# LEDcontroller.net
KiCad netlist of a schematic drawn in Altium Designer
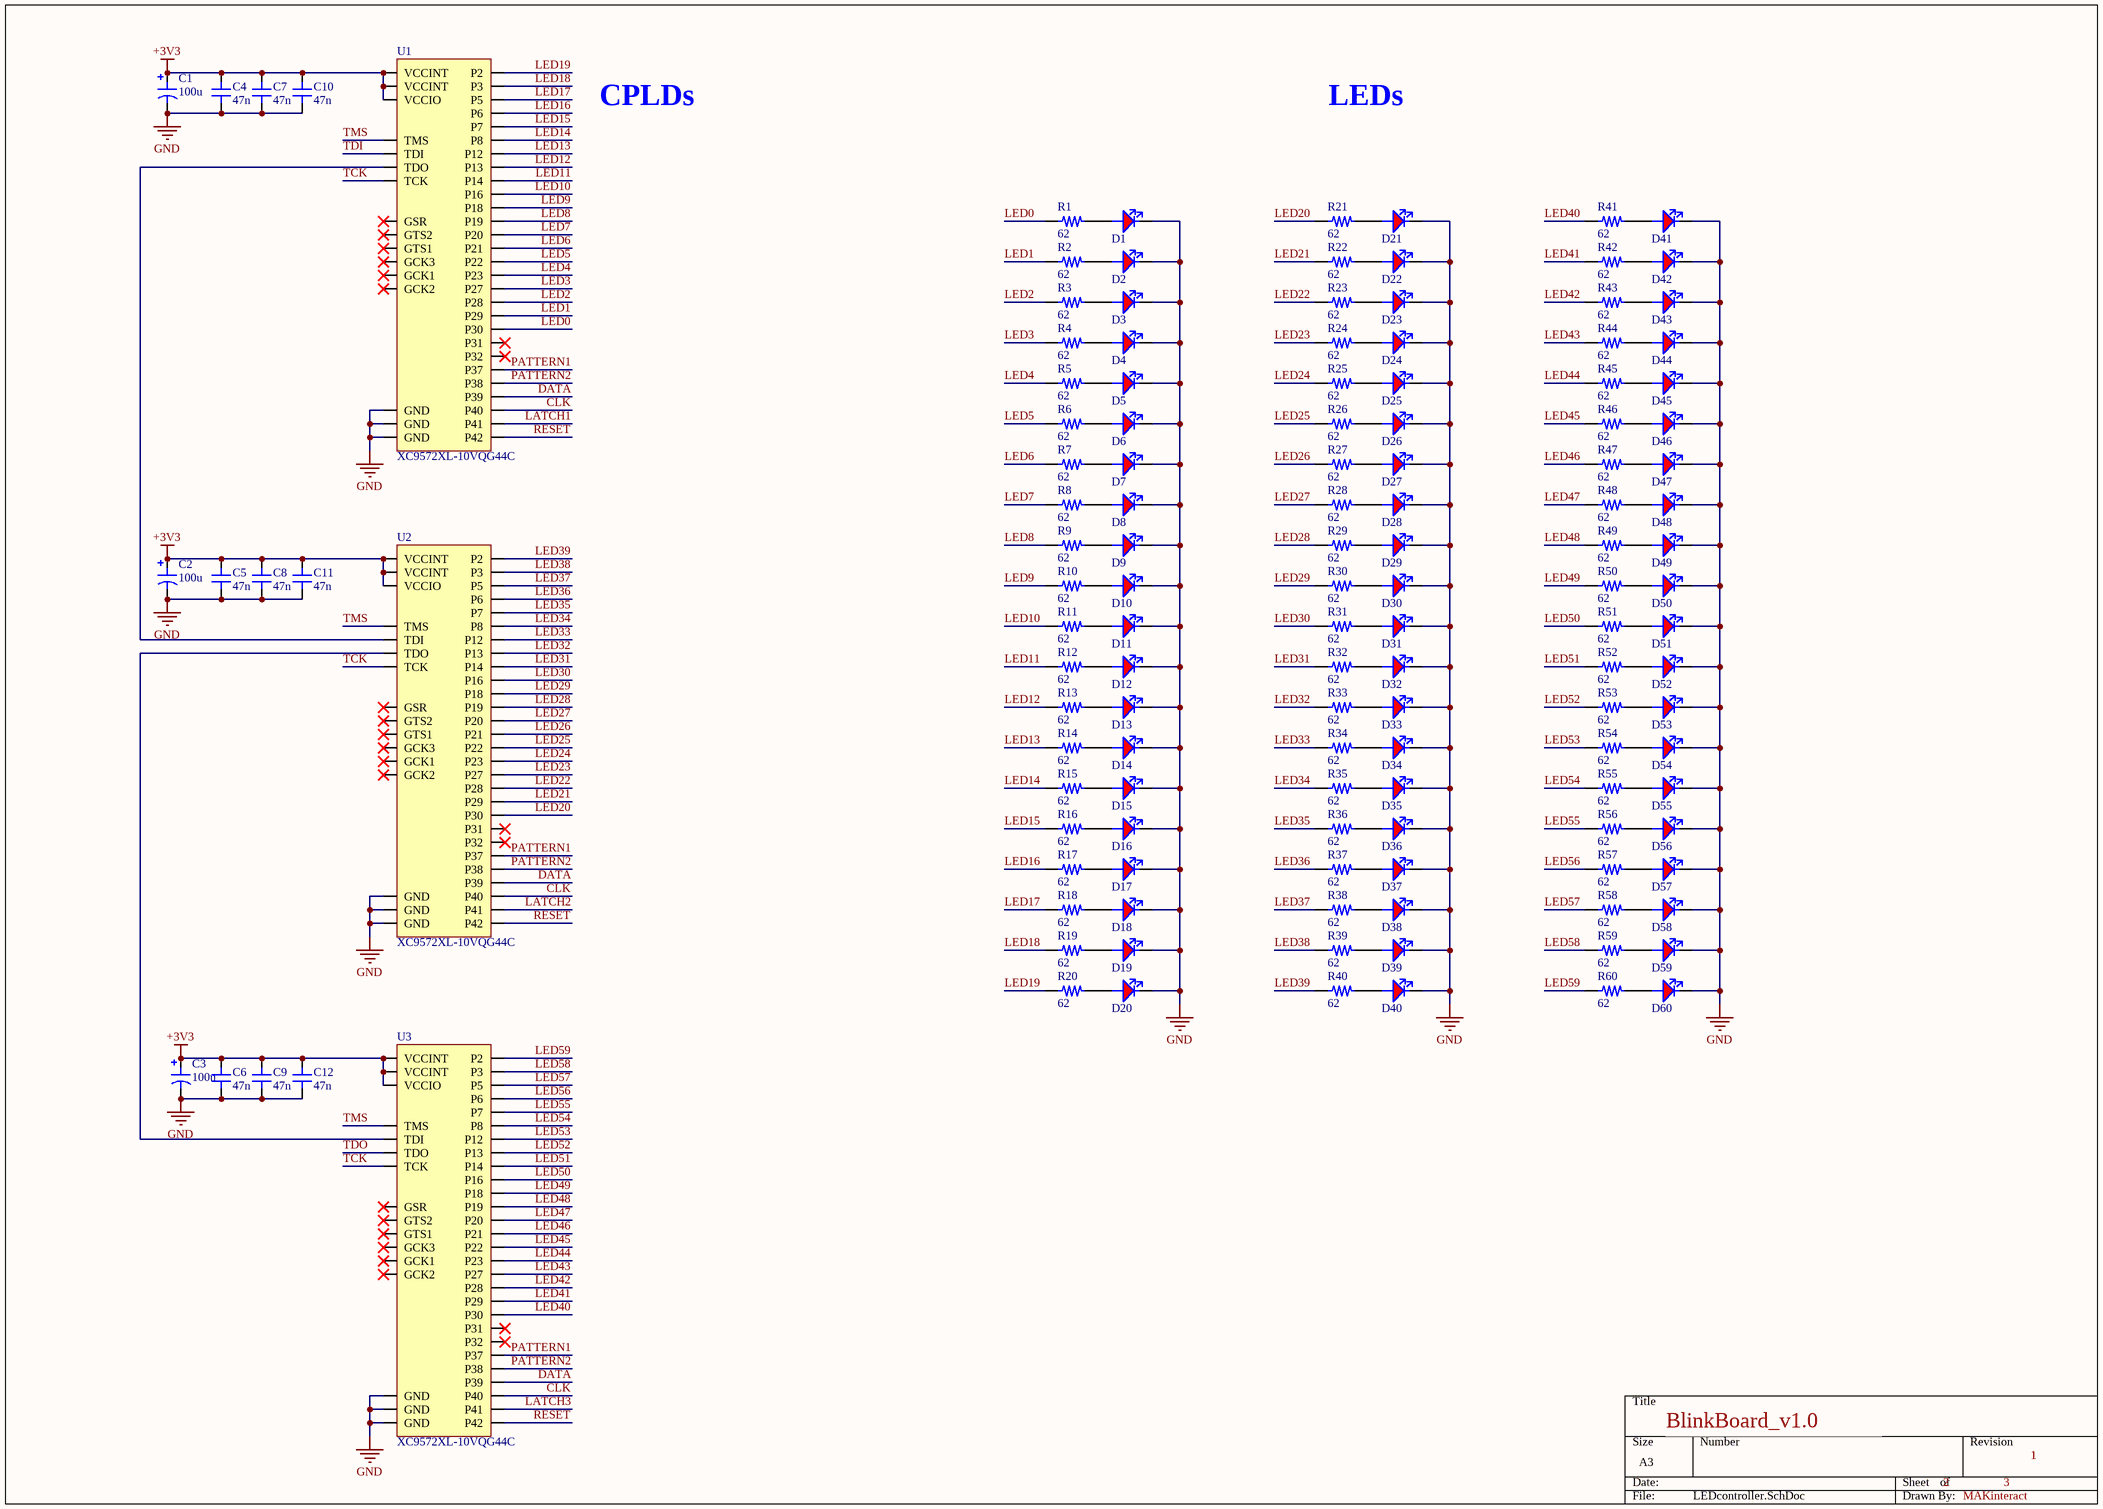
[diagram p0: LEDcontroller.SchDoc]

(export (version "E")
  (design (tool "Eeschema 10.0.6"))
  (components
    (comp (ref "C1")
      (value "100u")
      (footprint "C1206")
      (description "100uF Solid MnO2 Tantalum Capacitor,  4 V +/-20%,  T491 Series")
      (fields
        (field (name "MANUFACTURER") "KEMET")
        (field (name "MANUFACTURER PART NUMBER") "T491A107M004AT")
      )
      (libsource (lib "BlinkBoard") (part "C1206_100u"))
    )
    (comp (ref "C2")
      (value "100u")
      (footprint "C1206")
      (description "100uF Solid MnO2 Tantalum Capacitor,  4 V +/-20%,  T491 Series")
      (fields
        (field (name "MANUFACTURER") "KEMET")
        (field (name "MANUFACTURER PART NUMBER") "T491A107M004AT")
      )
      (libsource (lib "BlinkBoard") (part "C1206_100u"))
    )
    (comp (ref "C3")
      (value "100u")
      (footprint "C1206")
      (description "100uF Solid MnO2 Tantalum Capacitor,  4 V +/-20%,  T491 Series")
      (fields
        (field (name "MANUFACTURER") "KEMET")
        (field (name "MANUFACTURER PART NUMBER") "T491A107M004AT")
      )
      (libsource (lib "BlinkBoard") (part "C1206_100u"))
    )
    (comp (ref "C4")
      (value "47n")
      (footprint "C0805")
      (description "Cap Ceramic 0.047uF 50V X7R 5% SMD 0805 125C Paper T/R")
      (fields
        (field (name "MANUFACTURER") "Yageo")
        (field (name "MANUFACTURER PART NUMBER") "CC0805JRX7R9BB473")
      )
      (libsource (lib "LightBoard_v1.0") (part "C0805_47n"))
    )
    (comp (ref "C5")
      (value "47n")
      (footprint "C0805")
      (description "Cap Ceramic 0.047uF 50V X7R 5% SMD 0805 125C Paper T/R")
      (fields
        (field (name "MANUFACTURER") "Yageo")
        (field (name "MANUFACTURER PART NUMBER") "CC0805JRX7R9BB473")
      )
      (libsource (lib "LightBoard_v1.0") (part "C0805_47n"))
    )
    (comp (ref "C6")
      (value "47n")
      (footprint "C0805")
      (description "Cap Ceramic 0.047uF 50V X7R 5% SMD 0805 125C Paper T/R")
      (fields
        (field (name "MANUFACTURER") "Yageo")
        (field (name "MANUFACTURER PART NUMBER") "CC0805JRX7R9BB473")
      )
      (libsource (lib "LightBoard_v1.0") (part "C0805_47n"))
    )
    (comp (ref "C7")
      (value "47n")
      (footprint "C0805")
      (description "Cap Ceramic 0.047uF 50V X7R 5% SMD 0805 125C Paper T/R")
      (fields
        (field (name "MANUFACTURER") "Yageo")
        (field (name "MANUFACTURER PART NUMBER") "CC0805JRX7R9BB473")
      )
      (libsource (lib "LightBoard_v1.0") (part "C0805_47n"))
    )
    (comp (ref "C8")
      (value "47n")
      (footprint "C0805")
      (description "Cap Ceramic 0.047uF 50V X7R 5% SMD 0805 125C Paper T/R")
      (fields
        (field (name "MANUFACTURER") "Yageo")
        (field (name "MANUFACTURER PART NUMBER") "CC0805JRX7R9BB473")
      )
      (libsource (lib "LightBoard_v1.0") (part "C0805_47n"))
    )
    (comp (ref "C9")
      (value "47n")
      (footprint "C0805")
      (description "Cap Ceramic 0.047uF 50V X7R 5% SMD 0805 125C Paper T/R")
      (fields
        (field (name "MANUFACTURER") "Yageo")
        (field (name "MANUFACTURER PART NUMBER") "CC0805JRX7R9BB473")
      )
      (libsource (lib "LightBoard_v1.0") (part "C0805_47n"))
    )
    (comp (ref "C10")
      (value "47n")
      (footprint "C0805")
      (description "Cap Ceramic 0.047uF 50V X7R 5% SMD 0805 125C Paper T/R")
      (fields
        (field (name "MANUFACTURER") "Yageo")
        (field (name "MANUFACTURER PART NUMBER") "CC0805JRX7R9BB473")
      )
      (libsource (lib "LightBoard_v1.0") (part "C0805_47n"))
    )
    (comp (ref "C11")
      (value "47n")
      (footprint "C0805")
      (description "Cap Ceramic 0.047uF 50V X7R 5% SMD 0805 125C Paper T/R")
      (fields
        (field (name "MANUFACTURER") "Yageo")
        (field (name "MANUFACTURER PART NUMBER") "CC0805JRX7R9BB473")
      )
      (libsource (lib "LightBoard_v1.0") (part "C0805_47n"))
    )
    (comp (ref "C12")
      (value "47n")
      (footprint "C0805")
      (description "Cap Ceramic 0.047uF 50V X7R 5% SMD 0805 125C Paper T/R")
      (fields
        (field (name "MANUFACTURER") "Yageo")
        (field (name "MANUFACTURER PART NUMBER") "CC0805JRX7R9BB473")
      )
      (libsource (lib "LightBoard_v1.0") (part "C0805_47n"))
    )
    (comp (ref "D1")
      (value "LED0402_RED")
      (footprint "LED0402")
      (description "Led red")
      (fields
        (field (name "MANUFACTURER") "Everlight")
        (field (name "MANUFACTURER PART NUMBER") "EAST1005BA0")
      )
      (libsource (lib "LightBoard_v1.0") (part "LED0402_RED"))
    )
    (comp (ref "D2")
      (value "LED0402_RED")
      (footprint "LED0402")
      (description "Led red")
      (fields
        (field (name "MANUFACTURER") "Everlight")
        (field (name "MANUFACTURER PART NUMBER") "EAST1005BA0")
      )
      (libsource (lib "LightBoard_v1.0") (part "LED0402_RED"))
    )
    (comp (ref "D3")
      (value "LED0402_RED")
      (footprint "LED0402")
      (description "Led red")
      (fields
        (field (name "MANUFACTURER") "Everlight")
        (field (name "MANUFACTURER PART NUMBER") "EAST1005BA0")
      )
      (libsource (lib "LightBoard_v1.0") (part "LED0402_RED"))
    )
    (comp (ref "D4")
      (value "LED0402_RED")
      (footprint "LED0402")
      (description "Led red")
      (fields
        (field (name "MANUFACTURER") "Everlight")
        (field (name "MANUFACTURER PART NUMBER") "EAST1005BA0")
      )
      (libsource (lib "LightBoard_v1.0") (part "LED0402_RED"))
    )
    (comp (ref "D5")
      (value "LED0402_RED")
      (footprint "LED0402")
      (description "Led red")
      (fields
        (field (name "MANUFACTURER") "Everlight")
        (field (name "MANUFACTURER PART NUMBER") "EAST1005BA0")
      )
      (libsource (lib "LightBoard_v1.0") (part "LED0402_RED"))
    )
    (comp (ref "D6")
      (value "LED0402_RED")
      (footprint "LED0402")
      (description "Led red")
      (fields
        (field (name "MANUFACTURER") "Everlight")
        (field (name "MANUFACTURER PART NUMBER") "EAST1005BA0")
      )
      (libsource (lib "LightBoard_v1.0") (part "LED0402_RED"))
    )
    (comp (ref "D7")
      (value "LED0402_RED")
      (footprint "LED0402")
      (description "Led red")
      (fields
        (field (name "MANUFACTURER") "Everlight")
        (field (name "MANUFACTURER PART NUMBER") "EAST1005BA0")
      )
      (libsource (lib "LightBoard_v1.0") (part "LED0402_RED"))
    )
    (comp (ref "D8")
      (value "LED0402_RED")
      (footprint "LED0402")
      (description "Led red")
      (fields
        (field (name "MANUFACTURER") "Everlight")
        (field (name "MANUFACTURER PART NUMBER") "EAST1005BA0")
      )
      (libsource (lib "LightBoard_v1.0") (part "LED0402_RED"))
    )
    (comp (ref "D9")
      (value "LED0402_RED")
      (footprint "LED0402")
      (description "Led red")
      (fields
        (field (name "MANUFACTURER") "Everlight")
        (field (name "MANUFACTURER PART NUMBER") "EAST1005BA0")
      )
      (libsource (lib "LightBoard_v1.0") (part "LED0402_RED"))
    )
    (comp (ref "D10")
      (value "LED0402_RED")
      (footprint "LED0402")
      (description "Led red")
      (fields
        (field (name "MANUFACTURER") "Everlight")
        (field (name "MANUFACTURER PART NUMBER") "EAST1005BA0")
      )
      (libsource (lib "LightBoard_v1.0") (part "LED0402_RED"))
    )
    (comp (ref "D11")
      (value "LED0402_RED")
      (footprint "LED0402")
      (description "Led red")
      (fields
        (field (name "MANUFACTURER") "Everlight")
        (field (name "MANUFACTURER PART NUMBER") "EAST1005BA0")
      )
      (libsource (lib "LightBoard_v1.0") (part "LED0402_RED"))
    )
    (comp (ref "D12")
      (value "LED0402_RED")
      (footprint "LED0402")
      (description "Led red")
      (fields
        (field (name "MANUFACTURER") "Everlight")
        (field (name "MANUFACTURER PART NUMBER") "EAST1005BA0")
      )
      (libsource (lib "LightBoard_v1.0") (part "LED0402_RED"))
    )
    (comp (ref "D13")
      (value "LED0402_RED")
      (footprint "LED0402")
      (description "Led red")
      (fields
        (field (name "MANUFACTURER") "Everlight")
        (field (name "MANUFACTURER PART NUMBER") "EAST1005BA0")
      )
      (libsource (lib "LightBoard_v1.0") (part "LED0402_RED"))
    )
    (comp (ref "D14")
      (value "LED0402_RED")
      (footprint "LED0402")
      (description "Led red")
      (fields
        (field (name "MANUFACTURER") "Everlight")
        (field (name "MANUFACTURER PART NUMBER") "EAST1005BA0")
      )
      (libsource (lib "LightBoard_v1.0") (part "LED0402_RED"))
    )
    (comp (ref "D15")
      (value "LED0402_RED")
      (footprint "LED0402")
      (description "Led red")
      (fields
        (field (name "MANUFACTURER") "Everlight")
        (field (name "MANUFACTURER PART NUMBER") "EAST1005BA0")
      )
      (libsource (lib "LightBoard_v1.0") (part "LED0402_RED"))
    )
    (comp (ref "D16")
      (value "LED0402_RED")
      (footprint "LED0402")
      (description "Led red")
      (fields
        (field (name "MANUFACTURER") "Everlight")
        (field (name "MANUFACTURER PART NUMBER") "EAST1005BA0")
      )
      (libsource (lib "LightBoard_v1.0") (part "LED0402_RED"))
    )
    (comp (ref "D17")
      (value "LED0402_RED")
      (footprint "LED0402")
      (description "Led red")
      (fields
        (field (name "MANUFACTURER") "Everlight")
        (field (name "MANUFACTURER PART NUMBER") "EAST1005BA0")
      )
      (libsource (lib "LightBoard_v1.0") (part "LED0402_RED"))
    )
    (comp (ref "D18")
      (value "LED0402_RED")
      (footprint "LED0402")
      (description "Led red")
      (fields
        (field (name "MANUFACTURER") "Everlight")
        (field (name "MANUFACTURER PART NUMBER") "EAST1005BA0")
      )
      (libsource (lib "LightBoard_v1.0") (part "LED0402_RED"))
    )
    (comp (ref "D19")
      (value "LED0402_RED")
      (footprint "LED0402")
      (description "Led red")
      (fields
        (field (name "MANUFACTURER") "Everlight")
        (field (name "MANUFACTURER PART NUMBER") "EAST1005BA0")
      )
      (libsource (lib "LightBoard_v1.0") (part "LED0402_RED"))
    )
    (comp (ref "D20")
      (value "LED0402_RED")
      (footprint "LED0402")
      (description "Led red")
      (fields
        (field (name "MANUFACTURER") "Everlight")
        (field (name "MANUFACTURER PART NUMBER") "EAST1005BA0")
      )
      (libsource (lib "LightBoard_v1.0") (part "LED0402_RED"))
    )
    (comp (ref "D21")
      (value "LED0402_RED")
      (footprint "LED0402")
      (description "Led red")
      (fields
        (field (name "MANUFACTURER") "Everlight")
        (field (name "MANUFACTURER PART NUMBER") "EAST1005BA0")
      )
      (libsource (lib "LightBoard_v1.0") (part "LED0402_RED"))
    )
    (comp (ref "D22")
      (value "LED0402_RED")
      (footprint "LED0402")
      (description "Led red")
      (fields
        (field (name "MANUFACTURER") "Everlight")
        (field (name "MANUFACTURER PART NUMBER") "EAST1005BA0")
      )
      (libsource (lib "LightBoard_v1.0") (part "LED0402_RED"))
    )
    (comp (ref "D23")
      (value "LED0402_RED")
      (footprint "LED0402")
      (description "Led red")
      (fields
        (field (name "MANUFACTURER") "Everlight")
        (field (name "MANUFACTURER PART NUMBER") "EAST1005BA0")
      )
      (libsource (lib "LightBoard_v1.0") (part "LED0402_RED"))
    )
    (comp (ref "D24")
      (value "LED0402_RED")
      (footprint "LED0402")
      (description "Led red")
      (fields
        (field (name "MANUFACTURER") "Everlight")
        (field (name "MANUFACTURER PART NUMBER") "EAST1005BA0")
      )
      (libsource (lib "LightBoard_v1.0") (part "LED0402_RED"))
    )
    (comp (ref "D25")
      (value "LED0402_RED")
      (footprint "LED0402")
      (description "Led red")
      (fields
        (field (name "MANUFACTURER") "Everlight")
        (field (name "MANUFACTURER PART NUMBER") "EAST1005BA0")
      )
      (libsource (lib "LightBoard_v1.0") (part "LED0402_RED"))
    )
    (comp (ref "D26")
      (value "LED0402_RED")
      (footprint "LED0402")
      (description "Led red")
      (fields
        (field (name "MANUFACTURER") "Everlight")
        (field (name "MANUFACTURER PART NUMBER") "EAST1005BA0")
      )
      (libsource (lib "LightBoard_v1.0") (part "LED0402_RED"))
    )
    (comp (ref "D27")
      (value "LED0402_RED")
      (footprint "LED0402")
      (description "Led red")
      (fields
        (field (name "MANUFACTURER") "Everlight")
        (field (name "MANUFACTURER PART NUMBER") "EAST1005BA0")
      )
      (libsource (lib "LightBoard_v1.0") (part "LED0402_RED"))
    )
    (comp (ref "D28")
      (value "LED0402_RED")
      (footprint "LED0402")
      (description "Led red")
      (fields
        (field (name "MANUFACTURER") "Everlight")
        (field (name "MANUFACTURER PART NUMBER") "EAST1005BA0")
      )
      (libsource (lib "LightBoard_v1.0") (part "LED0402_RED"))
    )
    (comp (ref "D29")
      (value "LED0402_RED")
      (footprint "LED0402")
      (description "Led red")
      (fields
        (field (name "MANUFACTURER") "Everlight")
        (field (name "MANUFACTURER PART NUMBER") "EAST1005BA0")
      )
      (libsource (lib "LightBoard_v1.0") (part "LED0402_RED"))
    )
    (comp (ref "D30")
      (value "LED0402_RED")
      (footprint "LED0402")
      (description "Led red")
      (fields
        (field (name "MANUFACTURER") "Everlight")
        (field (name "MANUFACTURER PART NUMBER") "EAST1005BA0")
      )
      (libsource (lib "LightBoard_v1.0") (part "LED0402_RED"))
    )
    (comp (ref "D31")
      (value "LED0402_RED")
      (footprint "LED0402")
      (description "Led red")
      (fields
        (field (name "MANUFACTURER") "Everlight")
        (field (name "MANUFACTURER PART NUMBER") "EAST1005BA0")
      )
      (libsource (lib "LightBoard_v1.0") (part "LED0402_RED"))
    )
    (comp (ref "D32")
      (value "LED0402_RED")
      (footprint "LED0402")
      (description "Led red")
      (fields
        (field (name "MANUFACTURER") "Everlight")
        (field (name "MANUFACTURER PART NUMBER") "EAST1005BA0")
      )
      (libsource (lib "LightBoard_v1.0") (part "LED0402_RED"))
    )
    (comp (ref "D33")
      (value "LED0402_RED")
      (footprint "LED0402")
      (description "Led red")
      (fields
        (field (name "MANUFACTURER") "Everlight")
        (field (name "MANUFACTURER PART NUMBER") "EAST1005BA0")
      )
      (libsource (lib "LightBoard_v1.0") (part "LED0402_RED"))
    )
    (comp (ref "D34")
      (value "LED0402_RED")
      (footprint "LED0402")
      (description "Led red")
      (fields
        (field (name "MANUFACTURER") "Everlight")
        (field (name "MANUFACTURER PART NUMBER") "EAST1005BA0")
      )
      (libsource (lib "LightBoard_v1.0") (part "LED0402_RED"))
    )
    (comp (ref "D35")
      (value "LED0402_RED")
      (footprint "LED0402")
      (description "Led red")
      (fields
        (field (name "MANUFACTURER") "Everlight")
        (field (name "MANUFACTURER PART NUMBER") "EAST1005BA0")
      )
      (libsource (lib "LightBoard_v1.0") (part "LED0402_RED"))
    )
    (comp (ref "D36")
      (value "LED0402_RED")
      (footprint "LED0402")
      (description "Led red")
      (fields
        (field (name "MANUFACTURER") "Everlight")
        (field (name "MANUFACTURER PART NUMBER") "EAST1005BA0")
      )
      (libsource (lib "LightBoard_v1.0") (part "LED0402_RED"))
    )
    (comp (ref "D37")
      (value "LED0402_RED")
      (footprint "LED0402")
      (description "Led red")
      (fields
        (field (name "MANUFACTURER") "Everlight")
        (field (name "MANUFACTURER PART NUMBER") "EAST1005BA0")
      )
      (libsource (lib "LightBoard_v1.0") (part "LED0402_RED"))
    )
    (comp (ref "D38")
      (value "LED0402_RED")
      (footprint "LED0402")
      (description "Led red")
      (fields
        (field (name "MANUFACTURER") "Everlight")
        (field (name "MANUFACTURER PART NUMBER") "EAST1005BA0")
      )
      (libsource (lib "LightBoard_v1.0") (part "LED0402_RED"))
    )
    (comp (ref "D39")
      (value "LED0402_RED")
      (footprint "LED0402")
      (description "Led red")
      (fields
        (field (name "MANUFACTURER") "Everlight")
        (field (name "MANUFACTURER PART NUMBER") "EAST1005BA0")
      )
      (libsource (lib "LightBoard_v1.0") (part "LED0402_RED"))
    )
    (comp (ref "D40")
      (value "LED0402_RED")
      (footprint "LED0402")
      (description "Led red")
      (fields
        (field (name "MANUFACTURER") "Everlight")
        (field (name "MANUFACTURER PART NUMBER") "EAST1005BA0")
      )
      (libsource (lib "LightBoard_v1.0") (part "LED0402_RED"))
    )
    (comp (ref "D41")
      (value "LED0402_RED")
      (footprint "LED0402")
      (description "Led red")
      (fields
        (field (name "MANUFACTURER") "Everlight")
        (field (name "MANUFACTURER PART NUMBER") "EAST1005BA0")
      )
      (libsource (lib "LightBoard_v1.0") (part "LED0402_RED"))
    )
    (comp (ref "D42")
      (value "LED0402_RED")
      (footprint "LED0402")
      (description "Led red")
      (fields
        (field (name "MANUFACTURER") "Everlight")
        (field (name "MANUFACTURER PART NUMBER") "EAST1005BA0")
      )
      (libsource (lib "LightBoard_v1.0") (part "LED0402_RED"))
    )
    (comp (ref "D43")
      (value "LED0402_RED")
      (footprint "LED0402")
      (description "Led red")
      (fields
        (field (name "MANUFACTURER") "Everlight")
        (field (name "MANUFACTURER PART NUMBER") "EAST1005BA0")
      )
      (libsource (lib "LightBoard_v1.0") (part "LED0402_RED"))
    )
    (comp (ref "D44")
      (value "LED0402_RED")
      (footprint "LED0402")
      (description "Led red")
      (fields
        (field (name "MANUFACTURER") "Everlight")
        (field (name "MANUFACTURER PART NUMBER") "EAST1005BA0")
      )
      (libsource (lib "LightBoard_v1.0") (part "LED0402_RED"))
    )
    (comp (ref "D45")
      (value "LED0402_RED")
      (footprint "LED0402")
      (description "Led red")
      (fields
        (field (name "MANUFACTURER") "Everlight")
        (field (name "MANUFACTURER PART NUMBER") "EAST1005BA0")
      )
      (libsource (lib "LightBoard_v1.0") (part "LED0402_RED"))
    )
    (comp (ref "D46")
      (value "LED0402_RED")
      (footprint "LED0402")
      (description "Led red")
      (fields
        (field (name "MANUFACTURER") "Everlight")
        (field (name "MANUFACTURER PART NUMBER") "EAST1005BA0")
      )
      (libsource (lib "LightBoard_v1.0") (part "LED0402_RED"))
    )
    (comp (ref "D47")
      (value "LED0402_RED")
      (footprint "LED0402")
      (description "Led red")
      (fields
        (field (name "MANUFACTURER") "Everlight")
        (field (name "MANUFACTURER PART NUMBER") "EAST1005BA0")
      )
      (libsource (lib "LightBoard_v1.0") (part "LED0402_RED"))
    )
    (comp (ref "D48")
      (value "LED0402_RED")
      (footprint "LED0402")
      (description "Led red")
      (fields
        (field (name "MANUFACTURER") "Everlight")
        (field (name "MANUFACTURER PART NUMBER") "EAST1005BA0")
      )
      (libsource (lib "LightBoard_v1.0") (part "LED0402_RED"))
    )
    (comp (ref "D49")
      (value "LED0402_RED")
      (footprint "LED0402")
      (description "Led red")
      (fields
        (field (name "MANUFACTURER") "Everlight")
        (field (name "MANUFACTURER PART NUMBER") "EAST1005BA0")
      )
      (libsource (lib "LightBoard_v1.0") (part "LED0402_RED"))
    )
    (comp (ref "D50")
      (value "LED0402_RED")
      (footprint "LED0402")
      (description "Led red")
      (fields
        (field (name "MANUFACTURER") "Everlight")
        (field (name "MANUFACTURER PART NUMBER") "EAST1005BA0")
      )
      (libsource (lib "LightBoard_v1.0") (part "LED0402_RED"))
    )
    (comp (ref "D51")
      (value "LED0402_RED")
      (footprint "LED0402")
      (description "Led red")
      (fields
        (field (name "MANUFACTURER") "Everlight")
        (field (name "MANUFACTURER PART NUMBER") "EAST1005BA0")
      )
      (libsource (lib "LightBoard_v1.0") (part "LED0402_RED"))
    )
    (comp (ref "D52")
      (value "LED0402_RED")
      (footprint "LED0402")
      (description "Led red")
      (fields
        (field (name "MANUFACTURER") "Everlight")
        (field (name "MANUFACTURER PART NUMBER") "EAST1005BA0")
      )
      (libsource (lib "LightBoard_v1.0") (part "LED0402_RED"))
    )
    (comp (ref "D53")
      (value "LED0402_RED")
      (footprint "LED0402")
      (description "Led red")
      (fields
        (field (name "MANUFACTURER") "Everlight")
        (field (name "MANUFACTURER PART NUMBER") "EAST1005BA0")
      )
      (libsource (lib "LightBoard_v1.0") (part "LED0402_RED"))
    )
    (comp (ref "D54")
      (value "LED0402_RED")
      (footprint "LED0402")
      (description "Led red")
      (fields
        (field (name "MANUFACTURER") "Everlight")
        (field (name "MANUFACTURER PART NUMBER") "EAST1005BA0")
      )
      (libsource (lib "LightBoard_v1.0") (part "LED0402_RED"))
    )
    (comp (ref "D55")
      (value "LED0402_RED")
      (footprint "LED0402")
      (description "Led red")
      (fields
        (field (name "MANUFACTURER") "Everlight")
        (field (name "MANUFACTURER PART NUMBER") "EAST1005BA0")
      )
      (libsource (lib "LightBoard_v1.0") (part "LED0402_RED"))
    )
    (comp (ref "D56")
      (value "LED0402_RED")
      (footprint "LED0402")
      (description "Led red")
      (fields
        (field (name "MANUFACTURER") "Everlight")
        (field (name "MANUFACTURER PART NUMBER") "EAST1005BA0")
      )
      (libsource (lib "LightBoard_v1.0") (part "LED0402_RED"))
    )
    (comp (ref "D57")
      (value "LED0402_RED")
      (footprint "LED0402")
      (description "Led red")
      (fields
        (field (name "MANUFACTURER") "Everlight")
        (field (name "MANUFACTURER PART NUMBER") "EAST1005BA0")
      )
      (libsource (lib "LightBoard_v1.0") (part "LED0402_RED"))
    )
    (comp (ref "D58")
      (value "LED0402_RED")
      (footprint "LED0402")
      (description "Led red")
      (fields
        (field (name "MANUFACTURER") "Everlight")
        (field (name "MANUFACTURER PART NUMBER") "EAST1005BA0")
      )
      (libsource (lib "LightBoard_v1.0") (part "LED0402_RED"))
    )
    (comp (ref "D59")
      (value "LED0402_RED")
      (footprint "LED0402")
      (description "Led red")
      (fields
        (field (name "MANUFACTURER") "Everlight")
        (field (name "MANUFACTURER PART NUMBER") "EAST1005BA0")
      )
      (libsource (lib "LightBoard_v1.0") (part "LED0402_RED"))
    )
    (comp (ref "D60")
      (value "LED0402_RED")
      (footprint "LED0402")
      (description "Led red")
      (fields
        (field (name "MANUFACTURER") "Everlight")
        (field (name "MANUFACTURER PART NUMBER") "EAST1005BA0")
      )
      (libsource (lib "LightBoard_v1.0") (part "LED0402_RED"))
    )
    (comp (ref "R1")
      (value "62")
      (footprint "RES0402")
      (description "RES SMD 62 OHM 1% 1/16W 0402")
      (fields
        (field (name "MANUFACTURER") "Yageo")
        (field (name "MANUFACTURER PART NUMBER") "RC0402FR-0762RL")
      )
      (libsource (lib "LightBoard_v1.0") (part "R0402_62"))
    )
    (comp (ref "R2")
      (value "62")
      (footprint "RES0402")
      (description "RES SMD 62 OHM 1% 1/16W 0402")
      (fields
        (field (name "MANUFACTURER") "Yageo")
        (field (name "MANUFACTURER PART NUMBER") "RC0402FR-0762RL")
      )
      (libsource (lib "LightBoard_v1.0") (part "R0402_62"))
    )
    (comp (ref "R3")
      (value "62")
      (footprint "RES0402")
      (description "RES SMD 62 OHM 1% 1/16W 0402")
      (fields
        (field (name "MANUFACTURER") "Yageo")
        (field (name "MANUFACTURER PART NUMBER") "RC0402FR-0762RL")
      )
      (libsource (lib "LightBoard_v1.0") (part "R0402_62"))
    )
    (comp (ref "R4")
      (value "62")
      (footprint "RES0402")
      (description "RES SMD 62 OHM 1% 1/16W 0402")
      (fields
        (field (name "MANUFACTURER") "Yageo")
        (field (name "MANUFACTURER PART NUMBER") "RC0402FR-0762RL")
      )
      (libsource (lib "LightBoard_v1.0") (part "R0402_62"))
    )
    (comp (ref "R5")
      (value "62")
      (footprint "RES0402")
      (description "RES SMD 62 OHM 1% 1/16W 0402")
      (fields
        (field (name "MANUFACTURER") "Yageo")
        (field (name "MANUFACTURER PART NUMBER") "RC0402FR-0762RL")
      )
      (libsource (lib "LightBoard_v1.0") (part "R0402_62"))
    )
    (comp (ref "R6")
      (value "62")
      (footprint "RES0402")
      (description "RES SMD 62 OHM 1% 1/16W 0402")
      (fields
        (field (name "MANUFACTURER") "Yageo")
        (field (name "MANUFACTURER PART NUMBER") "RC0402FR-0762RL")
      )
      (libsource (lib "LightBoard_v1.0") (part "R0402_62"))
    )
    (comp (ref "R7")
      (value "62")
      (footprint "RES0402")
      (description "RES SMD 62 OHM 1% 1/16W 0402")
      (fields
        (field (name "MANUFACTURER") "Yageo")
        (field (name "MANUFACTURER PART NUMBER") "RC0402FR-0762RL")
      )
      (libsource (lib "LightBoard_v1.0") (part "R0402_62"))
    )
    (comp (ref "R8")
      (value "62")
      (footprint "RES0402")
      (description "RES SMD 62 OHM 1% 1/16W 0402")
      (fields
        (field (name "MANUFACTURER") "Yageo")
        (field (name "MANUFACTURER PART NUMBER") "RC0402FR-0762RL")
      )
      (libsource (lib "LightBoard_v1.0") (part "R0402_62"))
    )
    (comp (ref "R9")
      (value "62")
      (footprint "RES0402")
      (description "RES SMD 62 OHM 1% 1/16W 0402")
      (fields
        (field (name "MANUFACTURER") "Yageo")
        (field (name "MANUFACTURER PART NUMBER") "RC0402FR-0762RL")
      )
      (libsource (lib "LightBoard_v1.0") (part "R0402_62"))
    )
    (comp (ref "R10")
      (value "62")
      (footprint "RES0402")
      (description "RES SMD 62 OHM 1% 1/16W 0402")
      (fields
        (field (name "MANUFACTURER") "Yageo")
        (field (name "MANUFACTURER PART NUMBER") "RC0402FR-0762RL")
      )
      (libsource (lib "LightBoard_v1.0") (part "R0402_62"))
    )
    (comp (ref "R11")
      (value "62")
      (footprint "RES0402")
      (description "RES SMD 62 OHM 1% 1/16W 0402")
      (fields
        (field (name "MANUFACTURER") "Yageo")
        (field (name "MANUFACTURER PART NUMBER") "RC0402FR-0762RL")
      )
      (libsource (lib "LightBoard_v1.0") (part "R0402_62"))
    )
    (comp (ref "R12")
      (value "62")
      (footprint "RES0402")
      (description "RES SMD 62 OHM 1% 1/16W 0402")
      (fields
        (field (name "MANUFACTURER") "Yageo")
        (field (name "MANUFACTURER PART NUMBER") "RC0402FR-0762RL")
      )
      (libsource (lib "LightBoard_v1.0") (part "R0402_62"))
    )
    (comp (ref "R13")
      (value "62")
      (footprint "RES0402")
      (description "RES SMD 62 OHM 1% 1/16W 0402")
      (fields
        (field (name "MANUFACTURER") "Yageo")
        (field (name "MANUFACTURER PART NUMBER") "RC0402FR-0762RL")
      )
      (libsource (lib "LightBoard_v1.0") (part "R0402_62"))
    )
    (comp (ref "R14")
      (value "62")
      (footprint "RES0402")
      (description "RES SMD 62 OHM 1% 1/16W 0402")
      (fields
        (field (name "MANUFACTURER") "Yageo")
        (field (name "MANUFACTURER PART NUMBER") "RC0402FR-0762RL")
      )
      (libsource (lib "LightBoard_v1.0") (part "R0402_62"))
    )
    (comp (ref "R15")
      (value "62")
      (footprint "RES0402")
      (description "RES SMD 62 OHM 1% 1/16W 0402")
      (fields
        (field (name "MANUFACTURER") "Yageo")
        (field (name "MANUFACTURER PART NUMBER") "RC0402FR-0762RL")
      )
      (libsource (lib "LightBoard_v1.0") (part "R0402_62"))
    )
    (comp (ref "R16")
      (value "62")
      (footprint "RES0402")
      (description "RES SMD 62 OHM 1% 1/16W 0402")
      (fields
        (field (name "MANUFACTURER") "Yageo")
        (field (name "MANUFACTURER PART NUMBER") "RC0402FR-0762RL")
      )
      (libsource (lib "LightBoard_v1.0") (part "R0402_62"))
    )
    (comp (ref "R17")
      (value "62")
      (footprint "RES0402")
      (description "RES SMD 62 OHM 1% 1/16W 0402")
      (fields
        (field (name "MANUFACTURER") "Yageo")
        (field (name "MANUFACTURER PART NUMBER") "RC0402FR-0762RL")
      )
      (libsource (lib "LightBoard_v1.0") (part "R0402_62"))
    )
    (comp (ref "R18")
      (value "62")
      (footprint "RES0402")
      (description "RES SMD 62 OHM 1% 1/16W 0402")
      (fields
        (field (name "MANUFACTURER") "Yageo")
        (field (name "MANUFACTURER PART NUMBER") "RC0402FR-0762RL")
      )
      (libsource (lib "LightBoard_v1.0") (part "R0402_62"))
    )
    (comp (ref "R19")
      (value "62")
      (footprint "RES0402")
      (description "RES SMD 62 OHM 1% 1/16W 0402")
      (fields
        (field (name "MANUFACTURER") "Yageo")
        (field (name "MANUFACTURER PART NUMBER") "RC0402FR-0762RL")
      )
      (libsource (lib "LightBoard_v1.0") (part "R0402_62"))
    )
    (comp (ref "R20")
      (value "62")
      (footprint "RES0402")
      (description "RES SMD 62 OHM 1% 1/16W 0402")
      (fields
        (field (name "MANUFACTURER") "Yageo")
        (field (name "MANUFACTURER PART NUMBER") "RC0402FR-0762RL")
      )
      (libsource (lib "LightBoard_v1.0") (part "R0402_62"))
    )
    (comp (ref "R21")
      (value "62")
      (footprint "RES0402")
      (description "RES SMD 62 OHM 1% 1/16W 0402")
      (fields
        (field (name "MANUFACTURER") "Yageo")
        (field (name "MANUFACTURER PART NUMBER") "RC0402FR-0762RL")
      )
      (libsource (lib "LightBoard_v1.0") (part "R0402_62"))
    )
    (comp (ref "R22")
      (value "62")
      (footprint "RES0402")
      (description "RES SMD 62 OHM 1% 1/16W 0402")
      (fields
        (field (name "MANUFACTURER") "Yageo")
        (field (name "MANUFACTURER PART NUMBER") "RC0402FR-0762RL")
      )
      (libsource (lib "LightBoard_v1.0") (part "R0402_62"))
    )
    (comp (ref "R23")
      (value "62")
      (footprint "RES0402")
      (description "RES SMD 62 OHM 1% 1/16W 0402")
      (fields
        (field (name "MANUFACTURER") "Yageo")
        (field (name "MANUFACTURER PART NUMBER") "RC0402FR-0762RL")
      )
      (libsource (lib "LightBoard_v1.0") (part "R0402_62"))
    )
    (comp (ref "R24")
      (value "62")
      (footprint "RES0402")
      (description "RES SMD 62 OHM 1% 1/16W 0402")
      (fields
        (field (name "MANUFACTURER") "Yageo")
        (field (name "MANUFACTURER PART NUMBER") "RC0402FR-0762RL")
      )
      (libsource (lib "LightBoard_v1.0") (part "R0402_62"))
    )
    (comp (ref "R25")
      (value "62")
      (footprint "RES0402")
      (description "RES SMD 62 OHM 1% 1/16W 0402")
      (fields
        (field (name "MANUFACTURER") "Yageo")
        (field (name "MANUFACTURER PART NUMBER") "RC0402FR-0762RL")
      )
      (libsource (lib "LightBoard_v1.0") (part "R0402_62"))
    )
    (comp (ref "R26")
      (value "62")
      (footprint "RES0402")
      (description "RES SMD 62 OHM 1% 1/16W 0402")
      (fields
        (field (name "MANUFACTURER") "Yageo")
        (field (name "MANUFACTURER PART NUMBER") "RC0402FR-0762RL")
      )
      (libsource (lib "LightBoard_v1.0") (part "R0402_62"))
    )
    (comp (ref "R27")
      (value "62")
      (footprint "RES0402")
      (description "RES SMD 62 OHM 1% 1/16W 0402")
      (fields
        (field (name "MANUFACTURER") "Yageo")
        (field (name "MANUFACTURER PART NUMBER") "RC0402FR-0762RL")
      )
      (libsource (lib "LightBoard_v1.0") (part "R0402_62"))
    )
    (comp (ref "R28")
      (value "62")
      (footprint "RES0402")
      (description "RES SMD 62 OHM 1% 1/16W 0402")
      (fields
        (field (name "MANUFACTURER") "Yageo")
        (field (name "MANUFACTURER PART NUMBER") "RC0402FR-0762RL")
      )
      (libsource (lib "LightBoard_v1.0") (part "R0402_62"))
    )
    (comp (ref "R29")
      (value "62")
      (footprint "RES0402")
      (description "RES SMD 62 OHM 1% 1/16W 0402")
      (fields
        (field (name "MANUFACTURER") "Yageo")
        (field (name "MANUFACTURER PART NUMBER") "RC0402FR-0762RL")
      )
      (libsource (lib "LightBoard_v1.0") (part "R0402_62"))
    )
    (comp (ref "R30")
      (value "62")
      (footprint "RES0402")
      (description "RES SMD 62 OHM 1% 1/16W 0402")
      (fields
        (field (name "MANUFACTURER") "Yageo")
        (field (name "MANUFACTURER PART NUMBER") "RC0402FR-0762RL")
      )
      (libsource (lib "LightBoard_v1.0") (part "R0402_62"))
    )
    (comp (ref "R31")
      (value "62")
      (footprint "RES0402")
      (description "RES SMD 62 OHM 1% 1/16W 0402")
      (fields
        (field (name "MANUFACTURER") "Yageo")
        (field (name "MANUFACTURER PART NUMBER") "RC0402FR-0762RL")
      )
      (libsource (lib "LightBoard_v1.0") (part "R0402_62"))
    )
    (comp (ref "R32")
      (value "62")
      (footprint "RES0402")
      (description "RES SMD 62 OHM 1% 1/16W 0402")
      (fields
        (field (name "MANUFACTURER") "Yageo")
        (field (name "MANUFACTURER PART NUMBER") "RC0402FR-0762RL")
      )
      (libsource (lib "LightBoard_v1.0") (part "R0402_62"))
    )
    (comp (ref "R33")
      (value "62")
      (footprint "RES0402")
      (description "RES SMD 62 OHM 1% 1/16W 0402")
      (fields
        (field (name "MANUFACTURER") "Yageo")
        (field (name "MANUFACTURER PART NUMBER") "RC0402FR-0762RL")
      )
      (libsource (lib "LightBoard_v1.0") (part "R0402_62"))
    )
    (comp (ref "R34")
      (value "62")
      (footprint "RES0402")
      (description "RES SMD 62 OHM 1% 1/16W 0402")
      (fields
        (field (name "MANUFACTURER") "Yageo")
        (field (name "MANUFACTURER PART NUMBER") "RC0402FR-0762RL")
      )
      (libsource (lib "LightBoard_v1.0") (part "R0402_62"))
    )
    (comp (ref "R35")
      (value "62")
      (footprint "RES0402")
      (description "RES SMD 62 OHM 1% 1/16W 0402")
      (fields
        (field (name "MANUFACTURER") "Yageo")
        (field (name "MANUFACTURER PART NUMBER") "RC0402FR-0762RL")
      )
      (libsource (lib "LightBoard_v1.0") (part "R0402_62"))
    )
    (comp (ref "R36")
      (value "62")
      (footprint "RES0402")
      (description "RES SMD 62 OHM 1% 1/16W 0402")
      (fields
        (field (name "MANUFACTURER") "Yageo")
        (field (name "MANUFACTURER PART NUMBER") "RC0402FR-0762RL")
      )
      (libsource (lib "LightBoard_v1.0") (part "R0402_62"))
    )
    (comp (ref "R37")
      (value "62")
      (footprint "RES0402")
      (description "RES SMD 62 OHM 1% 1/16W 0402")
      (fields
        (field (name "MANUFACTURER") "Yageo")
        (field (name "MANUFACTURER PART NUMBER") "RC0402FR-0762RL")
      )
      (libsource (lib "LightBoard_v1.0") (part "R0402_62"))
    )
    (comp (ref "R38")
      (value "62")
      (footprint "RES0402")
      (description "RES SMD 62 OHM 1% 1/16W 0402")
      (fields
        (field (name "MANUFACTURER") "Yageo")
        (field (name "MANUFACTURER PART NUMBER") "RC0402FR-0762RL")
      )
      (libsource (lib "LightBoard_v1.0") (part "R0402_62"))
    )
    (comp (ref "R39")
      (value "62")
      (footprint "RES0402")
      (description "RES SMD 62 OHM 1% 1/16W 0402")
      (fields
        (field (name "MANUFACTURER") "Yageo")
        (field (name "MANUFACTURER PART NUMBER") "RC0402FR-0762RL")
      )
      (libsource (lib "LightBoard_v1.0") (part "R0402_62"))
    )
    (comp (ref "R40")
      (value "62")
      (footprint "RES0402")
      (description "RES SMD 62 OHM 1% 1/16W 0402")
      (fields
        (field (name "MANUFACTURER") "Yageo")
        (field (name "MANUFACTURER PART NUMBER") "RC0402FR-0762RL")
      )
      (libsource (lib "LightBoard_v1.0") (part "R0402_62"))
    )
    (comp (ref "R41")
      (value "62")
      (footprint "RES0402")
      (description "RES SMD 62 OHM 1% 1/16W 0402")
      (fields
        (field (name "MANUFACTURER") "Yageo")
        (field (name "MANUFACTURER PART NUMBER") "RC0402FR-0762RL")
      )
      (libsource (lib "LightBoard_v1.0") (part "R0402_62"))
    )
    (comp (ref "R42")
      (value "62")
      (footprint "RES0402")
      (description "RES SMD 62 OHM 1% 1/16W 0402")
      (fields
        (field (name "MANUFACTURER") "Yageo")
        (field (name "MANUFACTURER PART NUMBER") "RC0402FR-0762RL")
      )
      (libsource (lib "LightBoard_v1.0") (part "R0402_62"))
    )
    (comp (ref "R43")
      (value "62")
      (footprint "RES0402")
      (description "RES SMD 62 OHM 1% 1/16W 0402")
      (fields
        (field (name "MANUFACTURER") "Yageo")
        (field (name "MANUFACTURER PART NUMBER") "RC0402FR-0762RL")
      )
      (libsource (lib "LightBoard_v1.0") (part "R0402_62"))
    )
    (comp (ref "R44")
      (value "62")
      (footprint "RES0402")
      (description "RES SMD 62 OHM 1% 1/16W 0402")
      (fields
        (field (name "MANUFACTURER") "Yageo")
        (field (name "MANUFACTURER PART NUMBER") "RC0402FR-0762RL")
      )
      (libsource (lib "LightBoard_v1.0") (part "R0402_62"))
    )
    (comp (ref "R45")
      (value "62")
      (footprint "RES0402")
      (description "RES SMD 62 OHM 1% 1/16W 0402")
      (fields
        (field (name "MANUFACTURER") "Yageo")
        (field (name "MANUFACTURER PART NUMBER") "RC0402FR-0762RL")
      )
      (libsource (lib "LightBoard_v1.0") (part "R0402_62"))
    )
    (comp (ref "R46")
      (value "62")
      (footprint "RES0402")
      (description "RES SMD 62 OHM 1% 1/16W 0402")
      (fields
        (field (name "MANUFACTURER") "Yageo")
        (field (name "MANUFACTURER PART NUMBER") "RC0402FR-0762RL")
      )
      (libsource (lib "LightBoard_v1.0") (part "R0402_62"))
    )
    (comp (ref "R47")
      (value "62")
      (footprint "RES0402")
      (description "RES SMD 62 OHM 1% 1/16W 0402")
      (fields
        (field (name "MANUFACTURER") "Yageo")
        (field (name "MANUFACTURER PART NUMBER") "RC0402FR-0762RL")
      )
      (libsource (lib "LightBoard_v1.0") (part "R0402_62"))
    )
    (comp (ref "R48")
      (value "62")
      (footprint "RES0402")
      (description "RES SMD 62 OHM 1% 1/16W 0402")
      (fields
        (field (name "MANUFACTURER") "Yageo")
        (field (name "MANUFACTURER PART NUMBER") "RC0402FR-0762RL")
      )
      (libsource (lib "LightBoard_v1.0") (part "R0402_62"))
    )
    (comp (ref "R49")
      (value "62")
      (footprint "RES0402")
      (description "RES SMD 62 OHM 1% 1/16W 0402")
      (fields
        (field (name "MANUFACTURER") "Yageo")
        (field (name "MANUFACTURER PART NUMBER") "RC0402FR-0762RL")
      )
      (libsource (lib "LightBoard_v1.0") (part "R0402_62"))
    )
    (comp (ref "R50")
      (value "62")
      (footprint "RES0402")
      (description "RES SMD 62 OHM 1% 1/16W 0402")
      (fields
        (field (name "MANUFACTURER") "Yageo")
        (field (name "MANUFACTURER PART NUMBER") "RC0402FR-0762RL")
      )
      (libsource (lib "LightBoard_v1.0") (part "R0402_62"))
    )
    (comp (ref "R51")
      (value "62")
      (footprint "RES0402")
      (description "RES SMD 62 OHM 1% 1/16W 0402")
      (fields
        (field (name "MANUFACTURER") "Yageo")
        (field (name "MANUFACTURER PART NUMBER") "RC0402FR-0762RL")
      )
      (libsource (lib "LightBoard_v1.0") (part "R0402_62"))
    )
    (comp (ref "R52")
      (value "62")
      (footprint "RES0402")
      (description "RES SMD 62 OHM 1% 1/16W 0402")
      (fields
        (field (name "MANUFACTURER") "Yageo")
        (field (name "MANUFACTURER PART NUMBER") "RC0402FR-0762RL")
      )
      (libsource (lib "LightBoard_v1.0") (part "R0402_62"))
    )
    (comp (ref "R53")
      (value "62")
      (footprint "RES0402")
      (description "RES SMD 62 OHM 1% 1/16W 0402")
      (fields
        (field (name "MANUFACTURER") "Yageo")
        (field (name "MANUFACTURER PART NUMBER") "RC0402FR-0762RL")
      )
      (libsource (lib "LightBoard_v1.0") (part "R0402_62"))
    )
    (comp (ref "R54")
      (value "62")
      (footprint "RES0402")
      (description "RES SMD 62 OHM 1% 1/16W 0402")
      (fields
        (field (name "MANUFACTURER") "Yageo")
        (field (name "MANUFACTURER PART NUMBER") "RC0402FR-0762RL")
      )
      (libsource (lib "LightBoard_v1.0") (part "R0402_62"))
    )
    (comp (ref "R55")
      (value "62")
      (footprint "RES0402")
      (description "RES SMD 62 OHM 1% 1/16W 0402")
      (fields
        (field (name "MANUFACTURER") "Yageo")
        (field (name "MANUFACTURER PART NUMBER") "RC0402FR-0762RL")
      )
      (libsource (lib "LightBoard_v1.0") (part "R0402_62"))
    )
    (comp (ref "R56")
      (value "62")
      (footprint "RES0402")
      (description "RES SMD 62 OHM 1% 1/16W 0402")
      (fields
        (field (name "MANUFACTURER") "Yageo")
        (field (name "MANUFACTURER PART NUMBER") "RC0402FR-0762RL")
      )
      (libsource (lib "LightBoard_v1.0") (part "R0402_62"))
    )
    (comp (ref "R57")
      (value "62")
      (footprint "RES0402")
      (description "RES SMD 62 OHM 1% 1/16W 0402")
      (fields
        (field (name "MANUFACTURER") "Yageo")
        (field (name "MANUFACTURER PART NUMBER") "RC0402FR-0762RL")
      )
      (libsource (lib "LightBoard_v1.0") (part "R0402_62"))
    )
    (comp (ref "R58")
      (value "62")
      (footprint "RES0402")
      (description "RES SMD 62 OHM 1% 1/16W 0402")
      (fields
        (field (name "MANUFACTURER") "Yageo")
        (field (name "MANUFACTURER PART NUMBER") "RC0402FR-0762RL")
      )
      (libsource (lib "LightBoard_v1.0") (part "R0402_62"))
    )
    (comp (ref "R59")
      (value "62")
      (footprint "RES0402")
      (description "RES SMD 62 OHM 1% 1/16W 0402")
      (fields
        (field (name "MANUFACTURER") "Yageo")
        (field (name "MANUFACTURER PART NUMBER") "RC0402FR-0762RL")
      )
      (libsource (lib "LightBoard_v1.0") (part "R0402_62"))
    )
    (comp (ref "R60")
      (value "62")
      (footprint "RES0402")
      (description "RES SMD 62 OHM 1% 1/16W 0402")
      (fields
        (field (name "MANUFACTURER") "Yageo")
        (field (name "MANUFACTURER PART NUMBER") "RC0402FR-0762RL")
      )
      (libsource (lib "LightBoard_v1.0") (part "R0402_62"))
    )
    (comp (ref "U1")
      (value "XC9572XL-10VQG44C")
      (footprint "VQFP44")
      (description "XILINX - XC9572XL-10VQG44C. - CPLD, 72 MACROCELL, 3.3V, 44VQFP")
      (fields (field (name "MANUFACTURER") "Xilinx") (field (name "TOLERANCE") "1%"))
      (libsource (lib "LightBoard_v1.0") (part "XC9572XL"))
    )
    (comp (ref "U2")
      (value "XC9572XL-10VQG44C")
      (footprint "VQFP44")
      (description "XILINX - XC9572XL-10VQG44C. - CPLD, 72 MACROCELL, 3.3V, 44VQFP")
      (fields (field (name "MANUFACTURER") "Xilinx") (field (name "TOLERANCE") "1%"))
      (libsource (lib "LightBoard_v1.0") (part "XC9572XL"))
    )
    (comp (ref "U3")
      (value "XC9572XL-10VQG44C")
      (footprint "VQFP44")
      (description "XILINX - XC9572XL-10VQG44C. - CPLD, 72 MACROCELL, 3.3V, 44VQFP")
      (fields (field (name "MANUFACTURER") "Xilinx") (field (name "TOLERANCE") "1%"))
      (libsource (lib "LightBoard_v1.0") (part "XC9572XL"))
    )
  )
  (nets
    (net (code "1") (name "+3V3") (class "Default")
      (node (ref "C1") (pin "2") (pinfunction "2_2") (pintype "passive"))
      (node (ref "C10") (pin "2") (pinfunction "2_2") (pintype "passive"))
      (node (ref "C11") (pin "2") (pinfunction "2_2") (pintype "passive"))
      (node (ref "C12") (pin "2") (pinfunction "2_2") (pintype "passive"))
      (node (ref "C2") (pin "2") (pinfunction "2_2") (pintype "passive"))
      (node (ref "C3") (pin "2") (pinfunction "2_2") (pintype "passive"))
      (node (ref "C4") (pin "2") (pinfunction "2_2") (pintype "passive"))
      (node (ref "C5") (pin "2") (pinfunction "2_2") (pintype "passive"))
      (node (ref "C6") (pin "2") (pinfunction "2_2") (pintype "passive"))
      (node (ref "C7") (pin "2") (pinfunction "2_2") (pintype "passive"))
      (node (ref "C8") (pin "2") (pinfunction "2_2") (pintype "passive"))
      (node (ref "C9") (pin "2") (pinfunction "2_2") (pintype "passive"))
      (node (ref "U1") (pin "15") (pinfunction "VCCINT_15") (pintype "passive"))
      (node (ref "U1") (pin "26") (pinfunction "VCCIO_26") (pintype "passive"))
      (node (ref "U1") (pin "35") (pinfunction "VCCINT_35") (pintype "passive"))
      (node (ref "U2") (pin "15") (pinfunction "VCCINT_15") (pintype "passive"))
      (node (ref "U2") (pin "26") (pinfunction "VCCIO_26") (pintype "passive"))
      (node (ref "U2") (pin "35") (pinfunction "VCCINT_35") (pintype "passive"))
      (node (ref "U3") (pin "15") (pinfunction "VCCINT_15") (pintype "passive"))
      (node (ref "U3") (pin "26") (pinfunction "VCCIO_26") (pintype "passive"))
      (node (ref "U3") (pin "35") (pinfunction "VCCINT_35") (pintype "passive"))
    )
    (net (code "2") (name "/CLK") (class "Default")
      (node (ref "U1") (pin "40") (pinfunction "P40_40") (pintype "passive"))
      (node (ref "U2") (pin "40") (pinfunction "P40_40") (pintype "passive"))
      (node (ref "U3") (pin "40") (pinfunction "P40_40") (pintype "passive"))
    )
    (net (code "3") (name "/DATA") (class "Default")
      (node (ref "U1") (pin "39") (pinfunction "P39_39") (pintype "passive"))
      (node (ref "U2") (pin "39") (pinfunction "P39_39") (pintype "passive"))
      (node (ref "U3") (pin "39") (pinfunction "P39_39") (pintype "passive"))
    )
    (net (code "4") (name "/LATCH1") (class "Default")
      (node (ref "U1") (pin "41") (pinfunction "P41_41") (pintype "passive"))
    )
    (net (code "5") (name "/LATCH2") (class "Default")
      (node (ref "U2") (pin "41") (pinfunction "P41_41") (pintype "passive"))
    )
    (net (code "6") (name "/LATCH3") (class "Default")
      (node (ref "U3") (pin "41") (pinfunction "P41_41") (pintype "passive"))
    )
    (net (code "7") (name "/LED0") (class "Default")
      (node (ref "R1") (pin "1") (pinfunction "1_1") (pintype "passive"))
      (node (ref "U1") (pin "30") (pinfunction "P30_30") (pintype "passive"))
    )
    (net (code "8") (name "/LED1") (class "Default")
      (node (ref "R2") (pin "1") (pinfunction "1_1") (pintype "passive"))
      (node (ref "U1") (pin "29") (pinfunction "P29_29") (pintype "passive"))
    )
    (net (code "9") (name "/LED2") (class "Default")
      (node (ref "R3") (pin "1") (pinfunction "1_1") (pintype "passive"))
      (node (ref "U1") (pin "28") (pinfunction "P28_28") (pintype "passive"))
    )
    (net (code "10") (name "/LED3") (class "Default")
      (node (ref "R4") (pin "1") (pinfunction "1_1") (pintype "passive"))
      (node (ref "U1") (pin "27") (pinfunction "P27_27") (pintype "passive"))
    )
    (net (code "11") (name "/LED4") (class "Default")
      (node (ref "R5") (pin "1") (pinfunction "1_1") (pintype "passive"))
      (node (ref "U1") (pin "23") (pinfunction "P23_23") (pintype "passive"))
    )
    (net (code "12") (name "/LED5") (class "Default")
      (node (ref "R6") (pin "1") (pinfunction "1_1") (pintype "passive"))
      (node (ref "U1") (pin "22") (pinfunction "P22_22") (pintype "passive"))
    )
    (net (code "13") (name "/LED6") (class "Default")
      (node (ref "R7") (pin "1") (pinfunction "1_1") (pintype "passive"))
      (node (ref "U1") (pin "21") (pinfunction "P21_21") (pintype "passive"))
    )
    (net (code "14") (name "/LED7") (class "Default")
      (node (ref "R8") (pin "1") (pinfunction "1_1") (pintype "passive"))
      (node (ref "U1") (pin "20") (pinfunction "P20_20") (pintype "passive"))
    )
    (net (code "15") (name "/LED8") (class "Default")
      (node (ref "R9") (pin "1") (pinfunction "1_1") (pintype "passive"))
      (node (ref "U1") (pin "19") (pinfunction "P19_19") (pintype "passive"))
    )
    (net (code "16") (name "/LED9") (class "Default")
      (node (ref "R10") (pin "1") (pinfunction "1_1") (pintype "passive"))
      (node (ref "U1") (pin "18") (pinfunction "P18_18") (pintype "passive"))
    )
    (net (code "17") (name "/LED10") (class "Default")
      (node (ref "R11") (pin "1") (pinfunction "1_1") (pintype "passive"))
      (node (ref "U1") (pin "16") (pinfunction "P16_16") (pintype "passive"))
    )
    (net (code "18") (name "/LED11") (class "Default")
      (node (ref "R12") (pin "1") (pinfunction "1_1") (pintype "passive"))
      (node (ref "U1") (pin "14") (pinfunction "P14_14") (pintype "passive"))
    )
    (net (code "19") (name "/LED12") (class "Default")
      (node (ref "R13") (pin "1") (pinfunction "1_1") (pintype "passive"))
      (node (ref "U1") (pin "13") (pinfunction "P13_13") (pintype "passive"))
    )
    (net (code "20") (name "/LED13") (class "Default")
      (node (ref "R14") (pin "1") (pinfunction "1_1") (pintype "passive"))
      (node (ref "U1") (pin "12") (pinfunction "P12_12") (pintype "passive"))
    )
    (net (code "21") (name "/LED14") (class "Default")
      (node (ref "R15") (pin "1") (pinfunction "1_1") (pintype "passive"))
      (node (ref "U1") (pin "8") (pinfunction "P8_8") (pintype "passive"))
    )
    (net (code "22") (name "/LED15") (class "Default")
      (node (ref "R16") (pin "1") (pinfunction "1_1") (pintype "passive"))
      (node (ref "U1") (pin "7") (pinfunction "P7_7") (pintype "passive"))
    )
    (net (code "23") (name "/LED16") (class "Default")
      (node (ref "R17") (pin "1") (pinfunction "1_1") (pintype "passive"))
      (node (ref "U1") (pin "6") (pinfunction "P6_6") (pintype "passive"))
    )
    (net (code "24") (name "/LED17") (class "Default")
      (node (ref "R18") (pin "1") (pinfunction "1_1") (pintype "passive"))
      (node (ref "U1") (pin "5") (pinfunction "P5_5") (pintype "passive"))
    )
    (net (code "25") (name "/LED18") (class "Default")
      (node (ref "R19") (pin "1") (pinfunction "1_1") (pintype "passive"))
      (node (ref "U1") (pin "3") (pinfunction "P3_3") (pintype "passive"))
    )
    (net (code "26") (name "/LED19") (class "Default")
      (node (ref "R20") (pin "1") (pinfunction "1_1") (pintype "passive"))
      (node (ref "U1") (pin "2") (pinfunction "P2_2") (pintype "passive"))
    )
    (net (code "27") (name "/LED20") (class "Default")
      (node (ref "R21") (pin "1") (pinfunction "1_1") (pintype "passive"))
      (node (ref "U2") (pin "30") (pinfunction "P30_30") (pintype "passive"))
    )
    (net (code "28") (name "/LED21") (class "Default")
      (node (ref "R22") (pin "1") (pinfunction "1_1") (pintype "passive"))
      (node (ref "U2") (pin "29") (pinfunction "P29_29") (pintype "passive"))
    )
    (net (code "29") (name "/LED22") (class "Default")
      (node (ref "R23") (pin "1") (pinfunction "1_1") (pintype "passive"))
      (node (ref "U2") (pin "28") (pinfunction "P28_28") (pintype "passive"))
    )
    (net (code "30") (name "/LED23") (class "Default")
      (node (ref "R24") (pin "1") (pinfunction "1_1") (pintype "passive"))
      (node (ref "U2") (pin "27") (pinfunction "P27_27") (pintype "passive"))
    )
    (net (code "31") (name "/LED24") (class "Default")
      (node (ref "R25") (pin "1") (pinfunction "1_1") (pintype "passive"))
      (node (ref "U2") (pin "23") (pinfunction "P23_23") (pintype "passive"))
    )
    (net (code "32") (name "/LED25") (class "Default")
      (node (ref "R26") (pin "1") (pinfunction "1_1") (pintype "passive"))
      (node (ref "U2") (pin "22") (pinfunction "P22_22") (pintype "passive"))
    )
    (net (code "33") (name "/LED26") (class "Default")
      (node (ref "R27") (pin "1") (pinfunction "1_1") (pintype "passive"))
      (node (ref "U2") (pin "21") (pinfunction "P21_21") (pintype "passive"))
    )
    (net (code "34") (name "/LED27") (class "Default")
      (node (ref "R28") (pin "1") (pinfunction "1_1") (pintype "passive"))
      (node (ref "U2") (pin "20") (pinfunction "P20_20") (pintype "passive"))
    )
    (net (code "35") (name "/LED28") (class "Default")
      (node (ref "R29") (pin "1") (pinfunction "1_1") (pintype "passive"))
      (node (ref "U2") (pin "19") (pinfunction "P19_19") (pintype "passive"))
    )
    (net (code "36") (name "/LED29") (class "Default")
      (node (ref "R30") (pin "1") (pinfunction "1_1") (pintype "passive"))
      (node (ref "U2") (pin "18") (pinfunction "P18_18") (pintype "passive"))
    )
    (net (code "37") (name "/LED30") (class "Default")
      (node (ref "R31") (pin "1") (pinfunction "1_1") (pintype "passive"))
      (node (ref "U2") (pin "16") (pinfunction "P16_16") (pintype "passive"))
    )
    (net (code "38") (name "/LED31") (class "Default")
      (node (ref "R32") (pin "1") (pinfunction "1_1") (pintype "passive"))
      (node (ref "U2") (pin "14") (pinfunction "P14_14") (pintype "passive"))
    )
    (net (code "39") (name "/LED32") (class "Default")
      (node (ref "R33") (pin "1") (pinfunction "1_1") (pintype "passive"))
      (node (ref "U2") (pin "13") (pinfunction "P13_13") (pintype "passive"))
    )
    (net (code "40") (name "/LED33") (class "Default")
      (node (ref "R34") (pin "1") (pinfunction "1_1") (pintype "passive"))
      (node (ref "U2") (pin "12") (pinfunction "P12_12") (pintype "passive"))
    )
    (net (code "41") (name "/LED34") (class "Default")
      (node (ref "R35") (pin "1") (pinfunction "1_1") (pintype "passive"))
      (node (ref "U2") (pin "8") (pinfunction "P8_8") (pintype "passive"))
    )
    (net (code "42") (name "/LED35") (class "Default")
      (node (ref "R36") (pin "1") (pinfunction "1_1") (pintype "passive"))
      (node (ref "U2") (pin "7") (pinfunction "P7_7") (pintype "passive"))
    )
    (net (code "43") (name "/LED36") (class "Default")
      (node (ref "R37") (pin "1") (pinfunction "1_1") (pintype "passive"))
      (node (ref "U2") (pin "6") (pinfunction "P6_6") (pintype "passive"))
    )
    (net (code "44") (name "/LED37") (class "Default")
      (node (ref "R38") (pin "1") (pinfunction "1_1") (pintype "passive"))
      (node (ref "U2") (pin "5") (pinfunction "P5_5") (pintype "passive"))
    )
    (net (code "45") (name "/LED38") (class "Default")
      (node (ref "R39") (pin "1") (pinfunction "1_1") (pintype "passive"))
      (node (ref "U2") (pin "3") (pinfunction "P3_3") (pintype "passive"))
    )
    (net (code "46") (name "/LED39") (class "Default")
      (node (ref "R40") (pin "1") (pinfunction "1_1") (pintype "passive"))
      (node (ref "U2") (pin "2") (pinfunction "P2_2") (pintype "passive"))
    )
    (net (code "47") (name "/LED40") (class "Default")
      (node (ref "R41") (pin "1") (pinfunction "1_1") (pintype "passive"))
      (node (ref "U3") (pin "30") (pinfunction "P30_30") (pintype "passive"))
    )
    (net (code "48") (name "/LED41") (class "Default")
      (node (ref "R42") (pin "1") (pinfunction "1_1") (pintype "passive"))
      (node (ref "U3") (pin "29") (pinfunction "P29_29") (pintype "passive"))
    )
    (net (code "49") (name "/LED42") (class "Default")
      (node (ref "R43") (pin "1") (pinfunction "1_1") (pintype "passive"))
      (node (ref "U3") (pin "28") (pinfunction "P28_28") (pintype "passive"))
    )
    (net (code "50") (name "/LED43") (class "Default")
      (node (ref "R44") (pin "1") (pinfunction "1_1") (pintype "passive"))
      (node (ref "U3") (pin "27") (pinfunction "P27_27") (pintype "passive"))
    )
    (net (code "51") (name "/LED44") (class "Default")
      (node (ref "R45") (pin "1") (pinfunction "1_1") (pintype "passive"))
      (node (ref "U3") (pin "23") (pinfunction "P23_23") (pintype "passive"))
    )
    (net (code "52") (name "/LED45") (class "Default")
      (node (ref "R46") (pin "1") (pinfunction "1_1") (pintype "passive"))
      (node (ref "U3") (pin "22") (pinfunction "P22_22") (pintype "passive"))
    )
    (net (code "53") (name "/LED46") (class "Default")
      (node (ref "R47") (pin "1") (pinfunction "1_1") (pintype "passive"))
      (node (ref "U3") (pin "21") (pinfunction "P21_21") (pintype "passive"))
    )
    (net (code "54") (name "/LED47") (class "Default")
      (node (ref "R48") (pin "1") (pinfunction "1_1") (pintype "passive"))
      (node (ref "U3") (pin "20") (pinfunction "P20_20") (pintype "passive"))
    )
    (net (code "55") (name "/LED48") (class "Default")
      (node (ref "R49") (pin "1") (pinfunction "1_1") (pintype "passive"))
      (node (ref "U3") (pin "19") (pinfunction "P19_19") (pintype "passive"))
    )
    (net (code "56") (name "/LED49") (class "Default")
      (node (ref "R50") (pin "1") (pinfunction "1_1") (pintype "passive"))
      (node (ref "U3") (pin "18") (pinfunction "P18_18") (pintype "passive"))
    )
    (net (code "57") (name "/LED50") (class "Default")
      (node (ref "R51") (pin "1") (pinfunction "1_1") (pintype "passive"))
      (node (ref "U3") (pin "16") (pinfunction "P16_16") (pintype "passive"))
    )
    (net (code "58") (name "/LED51") (class "Default")
      (node (ref "R52") (pin "1") (pinfunction "1_1") (pintype "passive"))
      (node (ref "U3") (pin "14") (pinfunction "P14_14") (pintype "passive"))
    )
    (net (code "59") (name "/LED52") (class "Default")
      (node (ref "R53") (pin "1") (pinfunction "1_1") (pintype "passive"))
      (node (ref "U3") (pin "13") (pinfunction "P13_13") (pintype "passive"))
    )
    (net (code "60") (name "/LED53") (class "Default")
      (node (ref "R54") (pin "1") (pinfunction "1_1") (pintype "passive"))
      (node (ref "U3") (pin "12") (pinfunction "P12_12") (pintype "passive"))
    )
    (net (code "61") (name "/LED54") (class "Default")
      (node (ref "R55") (pin "1") (pinfunction "1_1") (pintype "passive"))
      (node (ref "U3") (pin "8") (pinfunction "P8_8") (pintype "passive"))
    )
    (net (code "62") (name "/LED55") (class "Default")
      (node (ref "R56") (pin "1") (pinfunction "1_1") (pintype "passive"))
      (node (ref "U3") (pin "7") (pinfunction "P7_7") (pintype "passive"))
    )
    (net (code "63") (name "/LED56") (class "Default")
      (node (ref "R57") (pin "1") (pinfunction "1_1") (pintype "passive"))
      (node (ref "U3") (pin "6") (pinfunction "P6_6") (pintype "passive"))
    )
    (net (code "64") (name "/LED57") (class "Default")
      (node (ref "R58") (pin "1") (pinfunction "1_1") (pintype "passive"))
      (node (ref "U3") (pin "5") (pinfunction "P5_5") (pintype "passive"))
    )
    (net (code "65") (name "/LED58") (class "Default")
      (node (ref "R59") (pin "1") (pinfunction "1_1") (pintype "passive"))
      (node (ref "U3") (pin "3") (pinfunction "P3_3") (pintype "passive"))
    )
    (net (code "66") (name "/LED59") (class "Default")
      (node (ref "R60") (pin "1") (pinfunction "1_1") (pintype "passive"))
      (node (ref "U3") (pin "2") (pinfunction "P2_2") (pintype "passive"))
    )
    (net (code "67") (name "/PATTERN1") (class "Default")
      (node (ref "U1") (pin "37") (pinfunction "P37_37") (pintype "passive"))
      (node (ref "U2") (pin "37") (pinfunction "P37_37") (pintype "passive"))
      (node (ref "U3") (pin "37") (pinfunction "P37_37") (pintype "passive"))
    )
    (net (code "68") (name "/PATTERN2") (class "Default")
      (node (ref "U1") (pin "38") (pinfunction "P38_38") (pintype "passive"))
      (node (ref "U2") (pin "38") (pinfunction "P38_38") (pintype "passive"))
      (node (ref "U3") (pin "38") (pinfunction "P38_38") (pintype "passive"))
    )
    (net (code "69") (name "/RESET") (class "Default")
      (node (ref "U1") (pin "42") (pinfunction "P42_42") (pintype "passive"))
      (node (ref "U2") (pin "42") (pinfunction "P42_42") (pintype "passive"))
      (node (ref "U3") (pin "42") (pinfunction "P42_42") (pintype "passive"))
    )
    (net (code "70") (name "/TCK") (class "Default")
      (node (ref "U1") (pin "11") (pinfunction "TCK_11") (pintype "passive"))
      (node (ref "U2") (pin "11") (pinfunction "TCK_11") (pintype "passive"))
      (node (ref "U3") (pin "11") (pinfunction "TCK_11") (pintype "passive"))
    )
    (net (code "71") (name "/TDI") (class "Default")
      (node (ref "U1") (pin "9") (pinfunction "TDI_9") (pintype "passive"))
    )
    (net (code "72") (name "/TDO") (class "Default")
      (node (ref "U3") (pin "24") (pinfunction "TDO_24") (pintype "passive"))
    )
    (net (code "73") (name "/TMS") (class "Default")
      (node (ref "U1") (pin "10") (pinfunction "TMS_10") (pintype "passive"))
      (node (ref "U2") (pin "10") (pinfunction "TMS_10") (pintype "passive"))
      (node (ref "U3") (pin "10") (pinfunction "TMS_10") (pintype "passive"))
    )
    (net (code "74") (name "GND") (class "Default")
      (node (ref "C1") (pin "1") (pinfunction "1_1") (pintype "passive"))
      (node (ref "C10") (pin "1") (pinfunction "1_1") (pintype "passive"))
      (node (ref "C11") (pin "1") (pinfunction "1_1") (pintype "passive"))
      (node (ref "C12") (pin "1") (pinfunction "1_1") (pintype "passive"))
      (node (ref "C2") (pin "1") (pinfunction "1_1") (pintype "passive"))
      (node (ref "C3") (pin "1") (pinfunction "1_1") (pintype "passive"))
      (node (ref "C4") (pin "1") (pinfunction "1_1") (pintype "passive"))
      (node (ref "C5") (pin "1") (pinfunction "1_1") (pintype "passive"))
      (node (ref "C6") (pin "1") (pinfunction "1_1") (pintype "passive"))
      (node (ref "C7") (pin "1") (pinfunction "1_1") (pintype "passive"))
      (node (ref "C8") (pin "1") (pinfunction "1_1") (pintype "passive"))
      (node (ref "C9") (pin "1") (pinfunction "1_1") (pintype "passive"))
      (node (ref "D1") (pin "2") (pinfunction "K_2") (pintype "passive"))
      (node (ref "D10") (pin "2") (pinfunction "K_2") (pintype "passive"))
      (node (ref "D11") (pin "2") (pinfunction "K_2") (pintype "passive"))
      (node (ref "D12") (pin "2") (pinfunction "K_2") (pintype "passive"))
      (node (ref "D13") (pin "2") (pinfunction "K_2") (pintype "passive"))
      (node (ref "D14") (pin "2") (pinfunction "K_2") (pintype "passive"))
      (node (ref "D15") (pin "2") (pinfunction "K_2") (pintype "passive"))
      (node (ref "D16") (pin "2") (pinfunction "K_2") (pintype "passive"))
      (node (ref "D17") (pin "2") (pinfunction "K_2") (pintype "passive"))
      (node (ref "D18") (pin "2") (pinfunction "K_2") (pintype "passive"))
      (node (ref "D19") (pin "2") (pinfunction "K_2") (pintype "passive"))
      (node (ref "D2") (pin "2") (pinfunction "K_2") (pintype "passive"))
      (node (ref "D20") (pin "2") (pinfunction "K_2") (pintype "passive"))
      (node (ref "D21") (pin "2") (pinfunction "K_2") (pintype "passive"))
      (node (ref "D22") (pin "2") (pinfunction "K_2") (pintype "passive"))
      (node (ref "D23") (pin "2") (pinfunction "K_2") (pintype "passive"))
      (node (ref "D24") (pin "2") (pinfunction "K_2") (pintype "passive"))
      (node (ref "D25") (pin "2") (pinfunction "K_2") (pintype "passive"))
      (node (ref "D26") (pin "2") (pinfunction "K_2") (pintype "passive"))
      (node (ref "D27") (pin "2") (pinfunction "K_2") (pintype "passive"))
      (node (ref "D28") (pin "2") (pinfunction "K_2") (pintype "passive"))
      (node (ref "D29") (pin "2") (pinfunction "K_2") (pintype "passive"))
      (node (ref "D3") (pin "2") (pinfunction "K_2") (pintype "passive"))
      (node (ref "D30") (pin "2") (pinfunction "K_2") (pintype "passive"))
      (node (ref "D31") (pin "2") (pinfunction "K_2") (pintype "passive"))
      (node (ref "D32") (pin "2") (pinfunction "K_2") (pintype "passive"))
      (node (ref "D33") (pin "2") (pinfunction "K_2") (pintype "passive"))
      (node (ref "D34") (pin "2") (pinfunction "K_2") (pintype "passive"))
      (node (ref "D35") (pin "2") (pinfunction "K_2") (pintype "passive"))
      (node (ref "D36") (pin "2") (pinfunction "K_2") (pintype "passive"))
      (node (ref "D37") (pin "2") (pinfunction "K_2") (pintype "passive"))
      (node (ref "D38") (pin "2") (pinfunction "K_2") (pintype "passive"))
      (node (ref "D39") (pin "2") (pinfunction "K_2") (pintype "passive"))
      (node (ref "D4") (pin "2") (pinfunction "K_2") (pintype "passive"))
      (node (ref "D40") (pin "2") (pinfunction "K_2") (pintype "passive"))
      (node (ref "D41") (pin "2") (pinfunction "K_2") (pintype "passive"))
      (node (ref "D42") (pin "2") (pinfunction "K_2") (pintype "passive"))
      (node (ref "D43") (pin "2") (pinfunction "K_2") (pintype "passive"))
      (node (ref "D44") (pin "2") (pinfunction "K_2") (pintype "passive"))
      (node (ref "D45") (pin "2") (pinfunction "K_2") (pintype "passive"))
      (node (ref "D46") (pin "2") (pinfunction "K_2") (pintype "passive"))
      (node (ref "D47") (pin "2") (pinfunction "K_2") (pintype "passive"))
      (node (ref "D48") (pin "2") (pinfunction "K_2") (pintype "passive"))
      (node (ref "D49") (pin "2") (pinfunction "K_2") (pintype "passive"))
      (node (ref "D5") (pin "2") (pinfunction "K_2") (pintype "passive"))
      (node (ref "D50") (pin "2") (pinfunction "K_2") (pintype "passive"))
      (node (ref "D51") (pin "2") (pinfunction "K_2") (pintype "passive"))
      (node (ref "D52") (pin "2") (pinfunction "K_2") (pintype "passive"))
      (node (ref "D53") (pin "2") (pinfunction "K_2") (pintype "passive"))
      (node (ref "D54") (pin "2") (pinfunction "K_2") (pintype "passive"))
      (node (ref "D55") (pin "2") (pinfunction "K_2") (pintype "passive"))
      (node (ref "D56") (pin "2") (pinfunction "K_2") (pintype "passive"))
      (node (ref "D57") (pin "2") (pinfunction "K_2") (pintype "passive"))
      (node (ref "D58") (pin "2") (pinfunction "K_2") (pintype "passive"))
      (node (ref "D59") (pin "2") (pinfunction "K_2") (pintype "passive"))
      (node (ref "D6") (pin "2") (pinfunction "K_2") (pintype "passive"))
      (node (ref "D60") (pin "2") (pinfunction "K_2") (pintype "passive"))
      (node (ref "D7") (pin "2") (pinfunction "K_2") (pintype "passive"))
      (node (ref "D8") (pin "2") (pinfunction "K_2") (pintype "passive"))
      (node (ref "D9") (pin "2") (pinfunction "K_2") (pintype "passive"))
      (node (ref "U1") (pin "17") (pinfunction "GND_17") (pintype "passive"))
      (node (ref "U1") (pin "25") (pinfunction "GND_25") (pintype "passive"))
      (node (ref "U1") (pin "4") (pinfunction "GND_4") (pintype "passive"))
      (node (ref "U2") (pin "17") (pinfunction "GND_17") (pintype "passive"))
      (node (ref "U2") (pin "25") (pinfunction "GND_25") (pintype "passive"))
      (node (ref "U2") (pin "4") (pinfunction "GND_4") (pintype "passive"))
      (node (ref "U3") (pin "17") (pinfunction "GND_17") (pintype "passive"))
      (node (ref "U3") (pin "25") (pinfunction "GND_25") (pintype "passive"))
      (node (ref "U3") (pin "4") (pinfunction "GND_4") (pintype "passive"))
    )
    (net (code "75") (name "Net-(D1-A)") (class "Default")
      (node (ref "D1") (pin "1") (pinfunction "A_1") (pintype "passive"))
      (node (ref "R1") (pin "2") (pinfunction "2_2") (pintype "passive"))
    )
    (net (code "76") (name "Net-(D2-A)") (class "Default")
      (node (ref "D2") (pin "1") (pinfunction "A_1") (pintype "passive"))
      (node (ref "R2") (pin "2") (pinfunction "2_2") (pintype "passive"))
    )
    (net (code "77") (name "Net-(D3-A)") (class "Default")
      (node (ref "D3") (pin "1") (pinfunction "A_1") (pintype "passive"))
      (node (ref "R3") (pin "2") (pinfunction "2_2") (pintype "passive"))
    )
    (net (code "78") (name "Net-(D4-A)") (class "Default")
      (node (ref "D4") (pin "1") (pinfunction "A_1") (pintype "passive"))
      (node (ref "R4") (pin "2") (pinfunction "2_2") (pintype "passive"))
    )
    (net (code "79") (name "Net-(D5-A)") (class "Default")
      (node (ref "D5") (pin "1") (pinfunction "A_1") (pintype "passive"))
      (node (ref "R5") (pin "2") (pinfunction "2_2") (pintype "passive"))
    )
    (net (code "80") (name "Net-(D6-A)") (class "Default")
      (node (ref "D6") (pin "1") (pinfunction "A_1") (pintype "passive"))
      (node (ref "R6") (pin "2") (pinfunction "2_2") (pintype "passive"))
    )
    (net (code "81") (name "Net-(D7-A)") (class "Default")
      (node (ref "D7") (pin "1") (pinfunction "A_1") (pintype "passive"))
      (node (ref "R7") (pin "2") (pinfunction "2_2") (pintype "passive"))
    )
    (net (code "82") (name "Net-(D8-A)") (class "Default")
      (node (ref "D8") (pin "1") (pinfunction "A_1") (pintype "passive"))
      (node (ref "R8") (pin "2") (pinfunction "2_2") (pintype "passive"))
    )
    (net (code "83") (name "Net-(D9-A)") (class "Default")
      (node (ref "D9") (pin "1") (pinfunction "A_1") (pintype "passive"))
      (node (ref "R9") (pin "2") (pinfunction "2_2") (pintype "passive"))
    )
    (net (code "84") (name "Net-(D10-A)") (class "Default")
      (node (ref "D10") (pin "1") (pinfunction "A_1") (pintype "passive"))
      (node (ref "R10") (pin "2") (pinfunction "2_2") (pintype "passive"))
    )
    (net (code "85") (name "Net-(D11-A)") (class "Default")
      (node (ref "D11") (pin "1") (pinfunction "A_1") (pintype "passive"))
      (node (ref "R11") (pin "2") (pinfunction "2_2") (pintype "passive"))
    )
    (net (code "86") (name "Net-(D12-A)") (class "Default")
      (node (ref "D12") (pin "1") (pinfunction "A_1") (pintype "passive"))
      (node (ref "R12") (pin "2") (pinfunction "2_2") (pintype "passive"))
    )
    (net (code "87") (name "Net-(D13-A)") (class "Default")
      (node (ref "D13") (pin "1") (pinfunction "A_1") (pintype "passive"))
      (node (ref "R13") (pin "2") (pinfunction "2_2") (pintype "passive"))
    )
    (net (code "88") (name "Net-(D14-A)") (class "Default")
      (node (ref "D14") (pin "1") (pinfunction "A_1") (pintype "passive"))
      (node (ref "R14") (pin "2") (pinfunction "2_2") (pintype "passive"))
    )
    (net (code "89") (name "Net-(D15-A)") (class "Default")
      (node (ref "D15") (pin "1") (pinfunction "A_1") (pintype "passive"))
      (node (ref "R15") (pin "2") (pinfunction "2_2") (pintype "passive"))
    )
    (net (code "90") (name "Net-(D16-A)") (class "Default")
      (node (ref "D16") (pin "1") (pinfunction "A_1") (pintype "passive"))
      (node (ref "R16") (pin "2") (pinfunction "2_2") (pintype "passive"))
    )
    (net (code "91") (name "Net-(D17-A)") (class "Default")
      (node (ref "D17") (pin "1") (pinfunction "A_1") (pintype "passive"))
      (node (ref "R17") (pin "2") (pinfunction "2_2") (pintype "passive"))
    )
    (net (code "92") (name "Net-(D18-A)") (class "Default")
      (node (ref "D18") (pin "1") (pinfunction "A_1") (pintype "passive"))
      (node (ref "R18") (pin "2") (pinfunction "2_2") (pintype "passive"))
    )
    (net (code "93") (name "Net-(D19-A)") (class "Default")
      (node (ref "D19") (pin "1") (pinfunction "A_1") (pintype "passive"))
      (node (ref "R19") (pin "2") (pinfunction "2_2") (pintype "passive"))
    )
    (net (code "94") (name "Net-(D20-A)") (class "Default")
      (node (ref "D20") (pin "1") (pinfunction "A_1") (pintype "passive"))
      (node (ref "R20") (pin "2") (pinfunction "2_2") (pintype "passive"))
    )
    (net (code "95") (name "Net-(D21-A)") (class "Default")
      (node (ref "D21") (pin "1") (pinfunction "A_1") (pintype "passive"))
      (node (ref "R21") (pin "2") (pinfunction "2_2") (pintype "passive"))
    )
    (net (code "96") (name "Net-(D22-A)") (class "Default")
      (node (ref "D22") (pin "1") (pinfunction "A_1") (pintype "passive"))
      (node (ref "R22") (pin "2") (pinfunction "2_2") (pintype "passive"))
    )
    (net (code "97") (name "Net-(D23-A)") (class "Default")
      (node (ref "D23") (pin "1") (pinfunction "A_1") (pintype "passive"))
      (node (ref "R23") (pin "2") (pinfunction "2_2") (pintype "passive"))
    )
    (net (code "98") (name "Net-(D24-A)") (class "Default")
      (node (ref "D24") (pin "1") (pinfunction "A_1") (pintype "passive"))
      (node (ref "R24") (pin "2") (pinfunction "2_2") (pintype "passive"))
    )
    (net (code "99") (name "Net-(D25-A)") (class "Default")
      (node (ref "D25") (pin "1") (pinfunction "A_1") (pintype "passive"))
      (node (ref "R25") (pin "2") (pinfunction "2_2") (pintype "passive"))
    )
    (net (code "100") (name "Net-(D26-A)") (class "Default")
      (node (ref "D26") (pin "1") (pinfunction "A_1") (pintype "passive"))
      (node (ref "R26") (pin "2") (pinfunction "2_2") (pintype "passive"))
    )
    (net (code "101") (name "Net-(D27-A)") (class "Default")
      (node (ref "D27") (pin "1") (pinfunction "A_1") (pintype "passive"))
      (node (ref "R27") (pin "2") (pinfunction "2_2") (pintype "passive"))
    )
    (net (code "102") (name "Net-(D28-A)") (class "Default")
      (node (ref "D28") (pin "1") (pinfunction "A_1") (pintype "passive"))
      (node (ref "R28") (pin "2") (pinfunction "2_2") (pintype "passive"))
    )
    (net (code "103") (name "Net-(D29-A)") (class "Default")
      (node (ref "D29") (pin "1") (pinfunction "A_1") (pintype "passive"))
      (node (ref "R29") (pin "2") (pinfunction "2_2") (pintype "passive"))
    )
    (net (code "104") (name "Net-(D30-A)") (class "Default")
      (node (ref "D30") (pin "1") (pinfunction "A_1") (pintype "passive"))
      (node (ref "R30") (pin "2") (pinfunction "2_2") (pintype "passive"))
    )
    (net (code "105") (name "Net-(D31-A)") (class "Default")
      (node (ref "D31") (pin "1") (pinfunction "A_1") (pintype "passive"))
      (node (ref "R31") (pin "2") (pinfunction "2_2") (pintype "passive"))
    )
    (net (code "106") (name "Net-(D32-A)") (class "Default")
      (node (ref "D32") (pin "1") (pinfunction "A_1") (pintype "passive"))
      (node (ref "R32") (pin "2") (pinfunction "2_2") (pintype "passive"))
    )
    (net (code "107") (name "Net-(D33-A)") (class "Default")
      (node (ref "D33") (pin "1") (pinfunction "A_1") (pintype "passive"))
      (node (ref "R33") (pin "2") (pinfunction "2_2") (pintype "passive"))
    )
    (net (code "108") (name "Net-(D34-A)") (class "Default")
      (node (ref "D34") (pin "1") (pinfunction "A_1") (pintype "passive"))
      (node (ref "R34") (pin "2") (pinfunction "2_2") (pintype "passive"))
    )
    (net (code "109") (name "Net-(D35-A)") (class "Default")
      (node (ref "D35") (pin "1") (pinfunction "A_1") (pintype "passive"))
      (node (ref "R35") (pin "2") (pinfunction "2_2") (pintype "passive"))
    )
    (net (code "110") (name "Net-(D36-A)") (class "Default")
      (node (ref "D36") (pin "1") (pinfunction "A_1") (pintype "passive"))
      (node (ref "R36") (pin "2") (pinfunction "2_2") (pintype "passive"))
    )
    (net (code "111") (name "Net-(D37-A)") (class "Default")
      (node (ref "D37") (pin "1") (pinfunction "A_1") (pintype "passive"))
      (node (ref "R37") (pin "2") (pinfunction "2_2") (pintype "passive"))
    )
    (net (code "112") (name "Net-(D38-A)") (class "Default")
      (node (ref "D38") (pin "1") (pinfunction "A_1") (pintype "passive"))
      (node (ref "R38") (pin "2") (pinfunction "2_2") (pintype "passive"))
    )
    (net (code "113") (name "Net-(D39-A)") (class "Default")
      (node (ref "D39") (pin "1") (pinfunction "A_1") (pintype "passive"))
      (node (ref "R39") (pin "2") (pinfunction "2_2") (pintype "passive"))
    )
    (net (code "114") (name "Net-(D40-A)") (class "Default")
      (node (ref "D40") (pin "1") (pinfunction "A_1") (pintype "passive"))
      (node (ref "R40") (pin "2") (pinfunction "2_2") (pintype "passive"))
    )
    (net (code "115") (name "Net-(D41-A)") (class "Default")
      (node (ref "D41") (pin "1") (pinfunction "A_1") (pintype "passive"))
      (node (ref "R41") (pin "2") (pinfunction "2_2") (pintype "passive"))
    )
    (net (code "116") (name "Net-(D42-A)") (class "Default")
      (node (ref "D42") (pin "1") (pinfunction "A_1") (pintype "passive"))
      (node (ref "R42") (pin "2") (pinfunction "2_2") (pintype "passive"))
    )
    (net (code "117") (name "Net-(D43-A)") (class "Default")
      (node (ref "D43") (pin "1") (pinfunction "A_1") (pintype "passive"))
      (node (ref "R43") (pin "2") (pinfunction "2_2") (pintype "passive"))
    )
    (net (code "118") (name "Net-(D44-A)") (class "Default")
      (node (ref "D44") (pin "1") (pinfunction "A_1") (pintype "passive"))
      (node (ref "R44") (pin "2") (pinfunction "2_2") (pintype "passive"))
    )
    (net (code "119") (name "Net-(D45-A)") (class "Default")
      (node (ref "D45") (pin "1") (pinfunction "A_1") (pintype "passive"))
      (node (ref "R45") (pin "2") (pinfunction "2_2") (pintype "passive"))
    )
    (net (code "120") (name "Net-(D46-A)") (class "Default")
      (node (ref "D46") (pin "1") (pinfunction "A_1") (pintype "passive"))
      (node (ref "R46") (pin "2") (pinfunction "2_2") (pintype "passive"))
    )
    (net (code "121") (name "Net-(D47-A)") (class "Default")
      (node (ref "D47") (pin "1") (pinfunction "A_1") (pintype "passive"))
      (node (ref "R47") (pin "2") (pinfunction "2_2") (pintype "passive"))
    )
    (net (code "122") (name "Net-(D48-A)") (class "Default")
      (node (ref "D48") (pin "1") (pinfunction "A_1") (pintype "passive"))
      (node (ref "R48") (pin "2") (pinfunction "2_2") (pintype "passive"))
    )
    (net (code "123") (name "Net-(D49-A)") (class "Default")
      (node (ref "D49") (pin "1") (pinfunction "A_1") (pintype "passive"))
      (node (ref "R49") (pin "2") (pinfunction "2_2") (pintype "passive"))
    )
    (net (code "124") (name "Net-(D50-A)") (class "Default")
      (node (ref "D50") (pin "1") (pinfunction "A_1") (pintype "passive"))
      (node (ref "R50") (pin "2") (pinfunction "2_2") (pintype "passive"))
    )
    (net (code "125") (name "Net-(D51-A)") (class "Default")
      (node (ref "D51") (pin "1") (pinfunction "A_1") (pintype "passive"))
      (node (ref "R51") (pin "2") (pinfunction "2_2") (pintype "passive"))
    )
    (net (code "126") (name "Net-(D52-A)") (class "Default")
      (node (ref "D52") (pin "1") (pinfunction "A_1") (pintype "passive"))
      (node (ref "R52") (pin "2") (pinfunction "2_2") (pintype "passive"))
    )
    (net (code "127") (name "Net-(D53-A)") (class "Default")
      (node (ref "D53") (pin "1") (pinfunction "A_1") (pintype "passive"))
      (node (ref "R53") (pin "2") (pinfunction "2_2") (pintype "passive"))
    )
    (net (code "128") (name "Net-(D54-A)") (class "Default")
      (node (ref "D54") (pin "1") (pinfunction "A_1") (pintype "passive"))
      (node (ref "R54") (pin "2") (pinfunction "2_2") (pintype "passive"))
    )
    (net (code "129") (name "Net-(D55-A)") (class "Default")
      (node (ref "D55") (pin "1") (pinfunction "A_1") (pintype "passive"))
      (node (ref "R55") (pin "2") (pinfunction "2_2") (pintype "passive"))
    )
    (net (code "130") (name "Net-(D56-A)") (class "Default")
      (node (ref "D56") (pin "1") (pinfunction "A_1") (pintype "passive"))
      (node (ref "R56") (pin "2") (pinfunction "2_2") (pintype "passive"))
    )
    (net (code "131") (name "Net-(D57-A)") (class "Default")
      (node (ref "D57") (pin "1") (pinfunction "A_1") (pintype "passive"))
      (node (ref "R57") (pin "2") (pinfunction "2_2") (pintype "passive"))
    )
    (net (code "132") (name "Net-(D58-A)") (class "Default")
      (node (ref "D58") (pin "1") (pinfunction "A_1") (pintype "passive"))
      (node (ref "R58") (pin "2") (pinfunction "2_2") (pintype "passive"))
    )
    (net (code "133") (name "Net-(D59-A)") (class "Default")
      (node (ref "D59") (pin "1") (pinfunction "A_1") (pintype "passive"))
      (node (ref "R59") (pin "2") (pinfunction "2_2") (pintype "passive"))
    )
    (net (code "134") (name "Net-(D60-A)") (class "Default")
      (node (ref "D60") (pin "1") (pinfunction "A_1") (pintype "passive"))
      (node (ref "R60") (pin "2") (pinfunction "2_2") (pintype "passive"))
    )
    (net (code "135") (name "Net-(U1-TDO)") (class "Default")
      (node (ref "U1") (pin "24") (pinfunction "TDO_24") (pintype "passive"))
      (node (ref "U2") (pin "9") (pinfunction "TDI_9") (pintype "passive"))
    )
    (net (code "136") (name "Net-(U2-TDO)") (class "Default")
      (node (ref "U2") (pin "24") (pinfunction "TDO_24") (pintype "passive"))
      (node (ref "U3") (pin "9") (pinfunction "TDI_9") (pintype "passive"))
    )
    (net (code "137") (name "unconnected-(U1-GCK1-Pad43)") (class "Default")
      (node (ref "U1") (pin "43") (pinfunction "GCK1_43") (pintype "passive+no_connect"))
    )
    (net (code "138") (name "unconnected-(U1-GCK2-Pad44)") (class "Default")
      (node (ref "U1") (pin "44") (pinfunction "GCK2_44") (pintype "passive+no_connect"))
    )
    (net (code "139") (name "unconnected-(U1-GCK3-Pad1)") (class "Default")
      (node (ref "U1") (pin "1") (pinfunction "GCK3_1") (pintype "passive+no_connect"))
    )
    (net (code "140") (name "unconnected-(U1-GSR-Pad33)") (class "Default")
      (node (ref "U1") (pin "33") (pinfunction "GSR_33") (pintype "passive+no_connect"))
    )
    (net (code "141") (name "unconnected-(U1-GTS1-Pad36)") (class "Default")
      (node (ref "U1") (pin "36") (pinfunction "GTS1_36") (pintype "passive+no_connect"))
    )
    (net (code "142") (name "unconnected-(U1-GTS2-Pad34)") (class "Default")
      (node (ref "U1") (pin "34") (pinfunction "GTS2_34") (pintype "passive+no_connect"))
    )
    (net (code "143") (name "unconnected-(U1-P31-Pad31)") (class "Default")
      (node (ref "U1") (pin "31") (pinfunction "P31_31") (pintype "passive+no_connect"))
    )
    (net (code "144") (name "unconnected-(U1-P32-Pad32)") (class "Default")
      (node (ref "U1") (pin "32") (pinfunction "P32_32") (pintype "passive+no_connect"))
    )
    (net (code "145") (name "unconnected-(U2-GCK1-Pad43)") (class "Default")
      (node (ref "U2") (pin "43") (pinfunction "GCK1_43") (pintype "passive+no_connect"))
    )
    (net (code "146") (name "unconnected-(U2-GCK2-Pad44)") (class "Default")
      (node (ref "U2") (pin "44") (pinfunction "GCK2_44") (pintype "passive+no_connect"))
    )
    (net (code "147") (name "unconnected-(U2-GCK3-Pad1)") (class "Default")
      (node (ref "U2") (pin "1") (pinfunction "GCK3_1") (pintype "passive+no_connect"))
    )
    (net (code "148") (name "unconnected-(U2-GSR-Pad33)") (class "Default")
      (node (ref "U2") (pin "33") (pinfunction "GSR_33") (pintype "passive+no_connect"))
    )
    (net (code "149") (name "unconnected-(U2-GTS1-Pad36)") (class "Default")
      (node (ref "U2") (pin "36") (pinfunction "GTS1_36") (pintype "passive+no_connect"))
    )
    (net (code "150") (name "unconnected-(U2-GTS2-Pad34)") (class "Default")
      (node (ref "U2") (pin "34") (pinfunction "GTS2_34") (pintype "passive+no_connect"))
    )
    (net (code "151") (name "unconnected-(U2-P31-Pad31)") (class "Default")
      (node (ref "U2") (pin "31") (pinfunction "P31_31") (pintype "passive+no_connect"))
    )
    (net (code "152") (name "unconnected-(U2-P32-Pad32)") (class "Default")
      (node (ref "U2") (pin "32") (pinfunction "P32_32") (pintype "passive+no_connect"))
    )
    (net (code "153") (name "unconnected-(U3-GCK1-Pad43)") (class "Default")
      (node (ref "U3") (pin "43") (pinfunction "GCK1_43") (pintype "passive+no_connect"))
    )
    (net (code "154") (name "unconnected-(U3-GCK2-Pad44)") (class "Default")
      (node (ref "U3") (pin "44") (pinfunction "GCK2_44") (pintype "passive+no_connect"))
    )
    (net (code "155") (name "unconnected-(U3-GCK3-Pad1)") (class "Default")
      (node (ref "U3") (pin "1") (pinfunction "GCK3_1") (pintype "passive+no_connect"))
    )
    (net (code "156") (name "unconnected-(U3-GSR-Pad33)") (class "Default")
      (node (ref "U3") (pin "33") (pinfunction "GSR_33") (pintype "passive+no_connect"))
    )
    (net (code "157") (name "unconnected-(U3-GTS1-Pad36)") (class "Default")
      (node (ref "U3") (pin "36") (pinfunction "GTS1_36") (pintype "passive+no_connect"))
    )
    (net (code "158") (name "unconnected-(U3-GTS2-Pad34)") (class "Default")
      (node (ref "U3") (pin "34") (pinfunction "GTS2_34") (pintype "passive+no_connect"))
    )
    (net (code "159") (name "unconnected-(U3-P31-Pad31)") (class "Default")
      (node (ref "U3") (pin "31") (pinfunction "P31_31") (pintype "passive+no_connect"))
    )
    (net (code "160") (name "unconnected-(U3-P32-Pad32)") (class "Default")
      (node (ref "U3") (pin "32") (pinfunction "P32_32") (pintype "passive+no_connect"))
    )
  )
)
